# EEZ_CF-DIC_r3B8.net
KiCad netlist of a schematic drawn in EAGLE
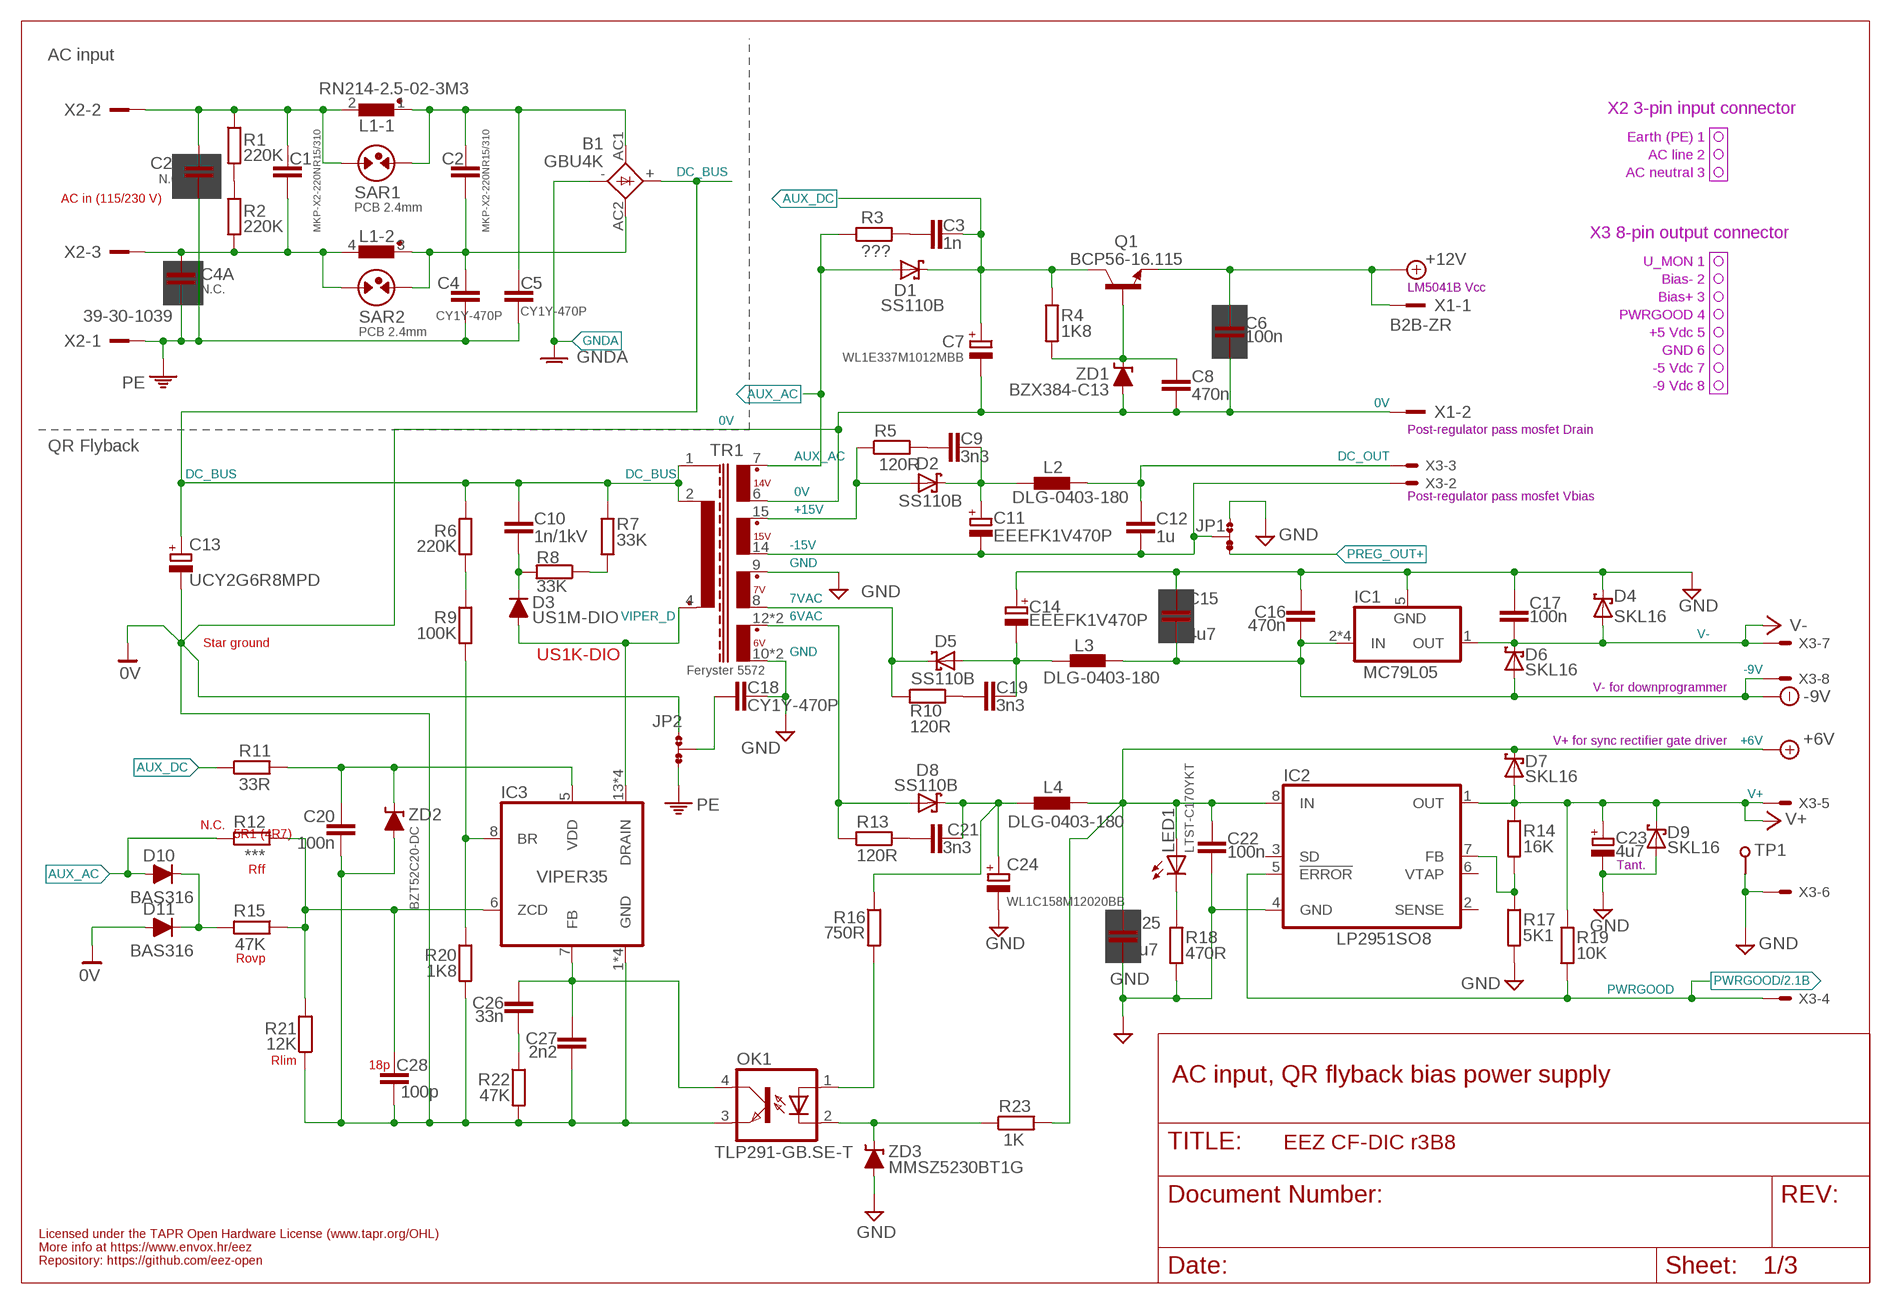
[diagram p0: schematic, sheet 1]
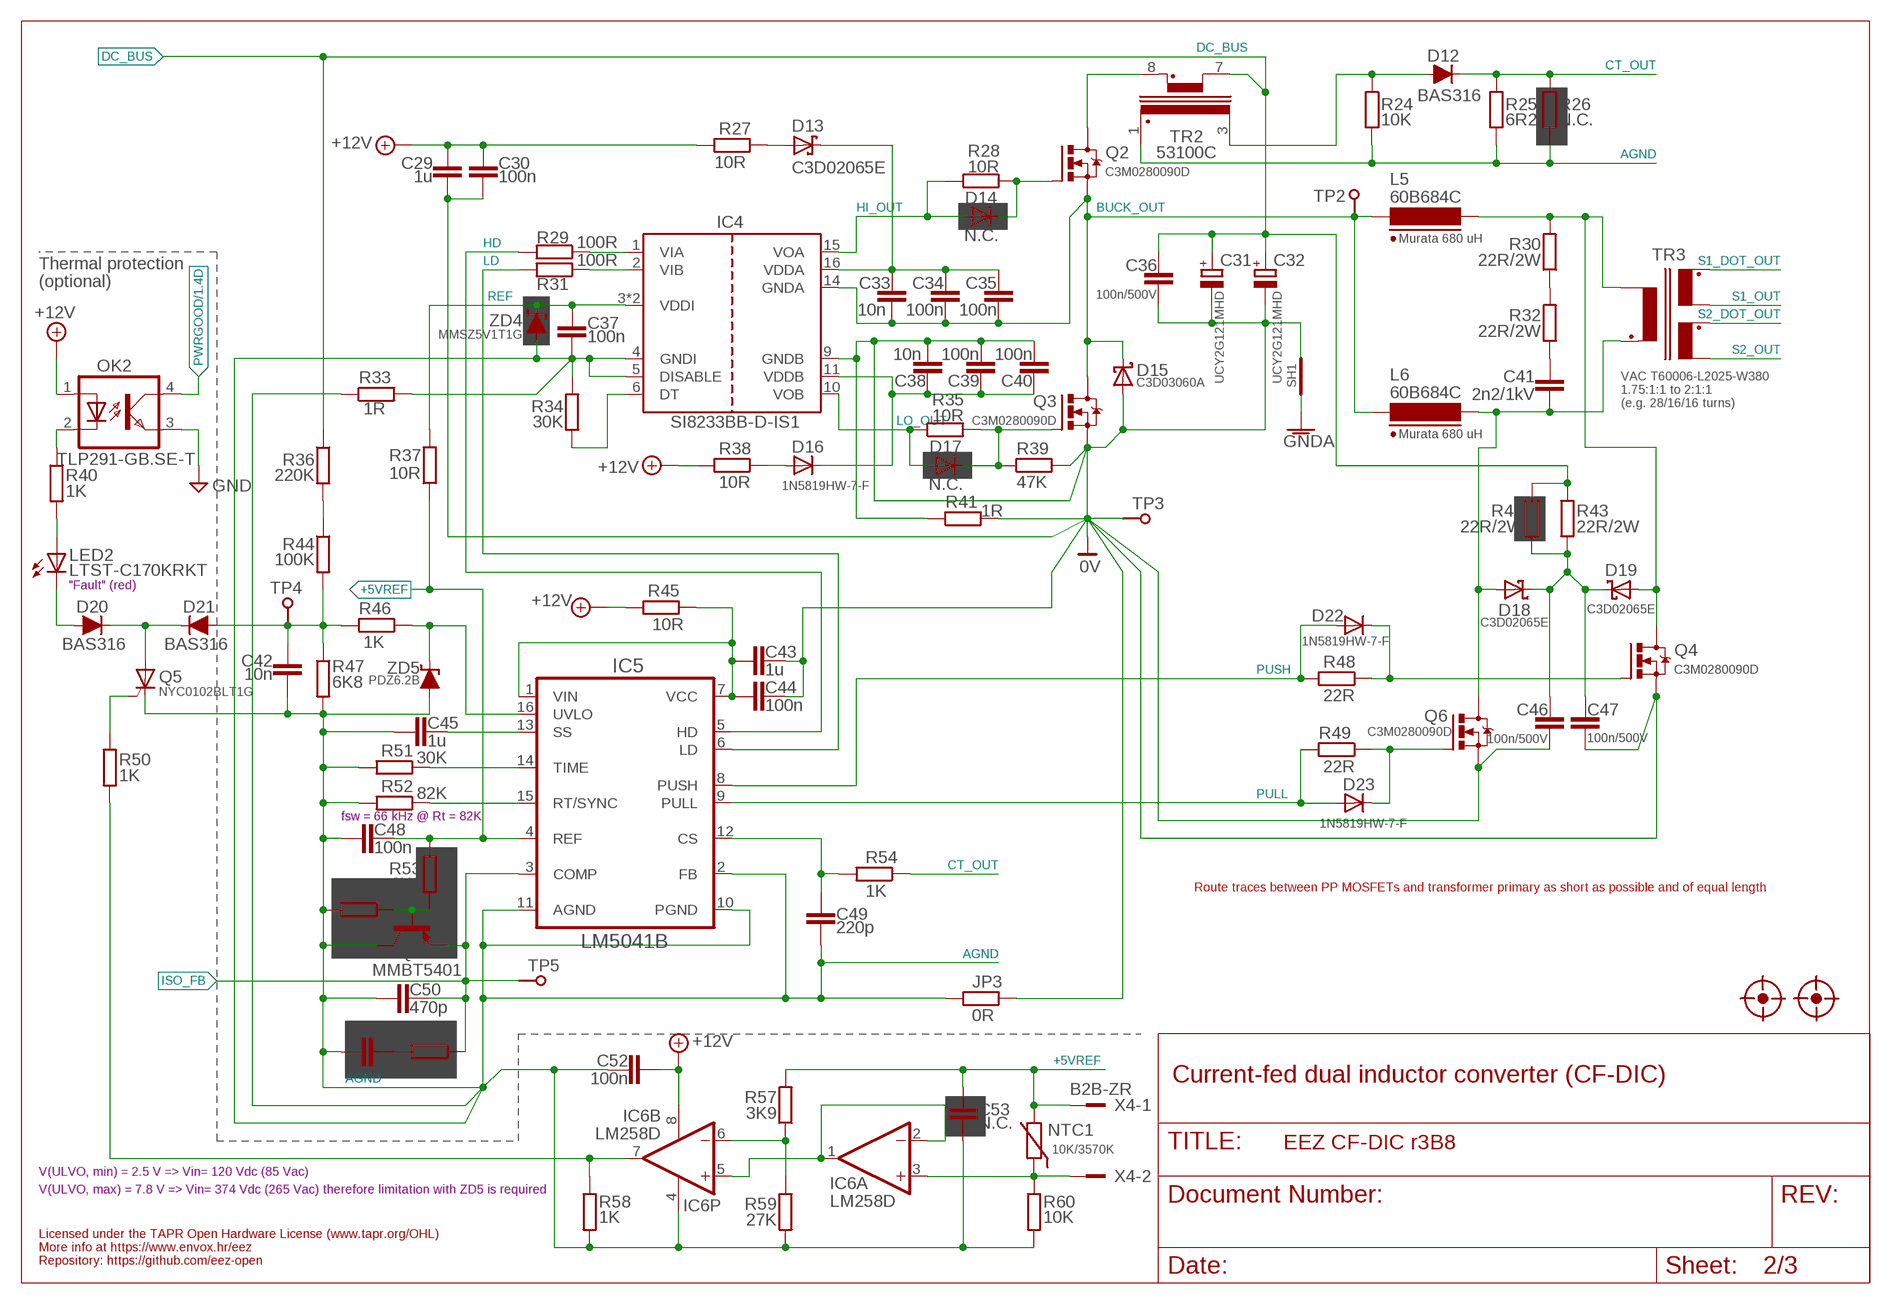
[diagram p1: schematic, sheet 2]
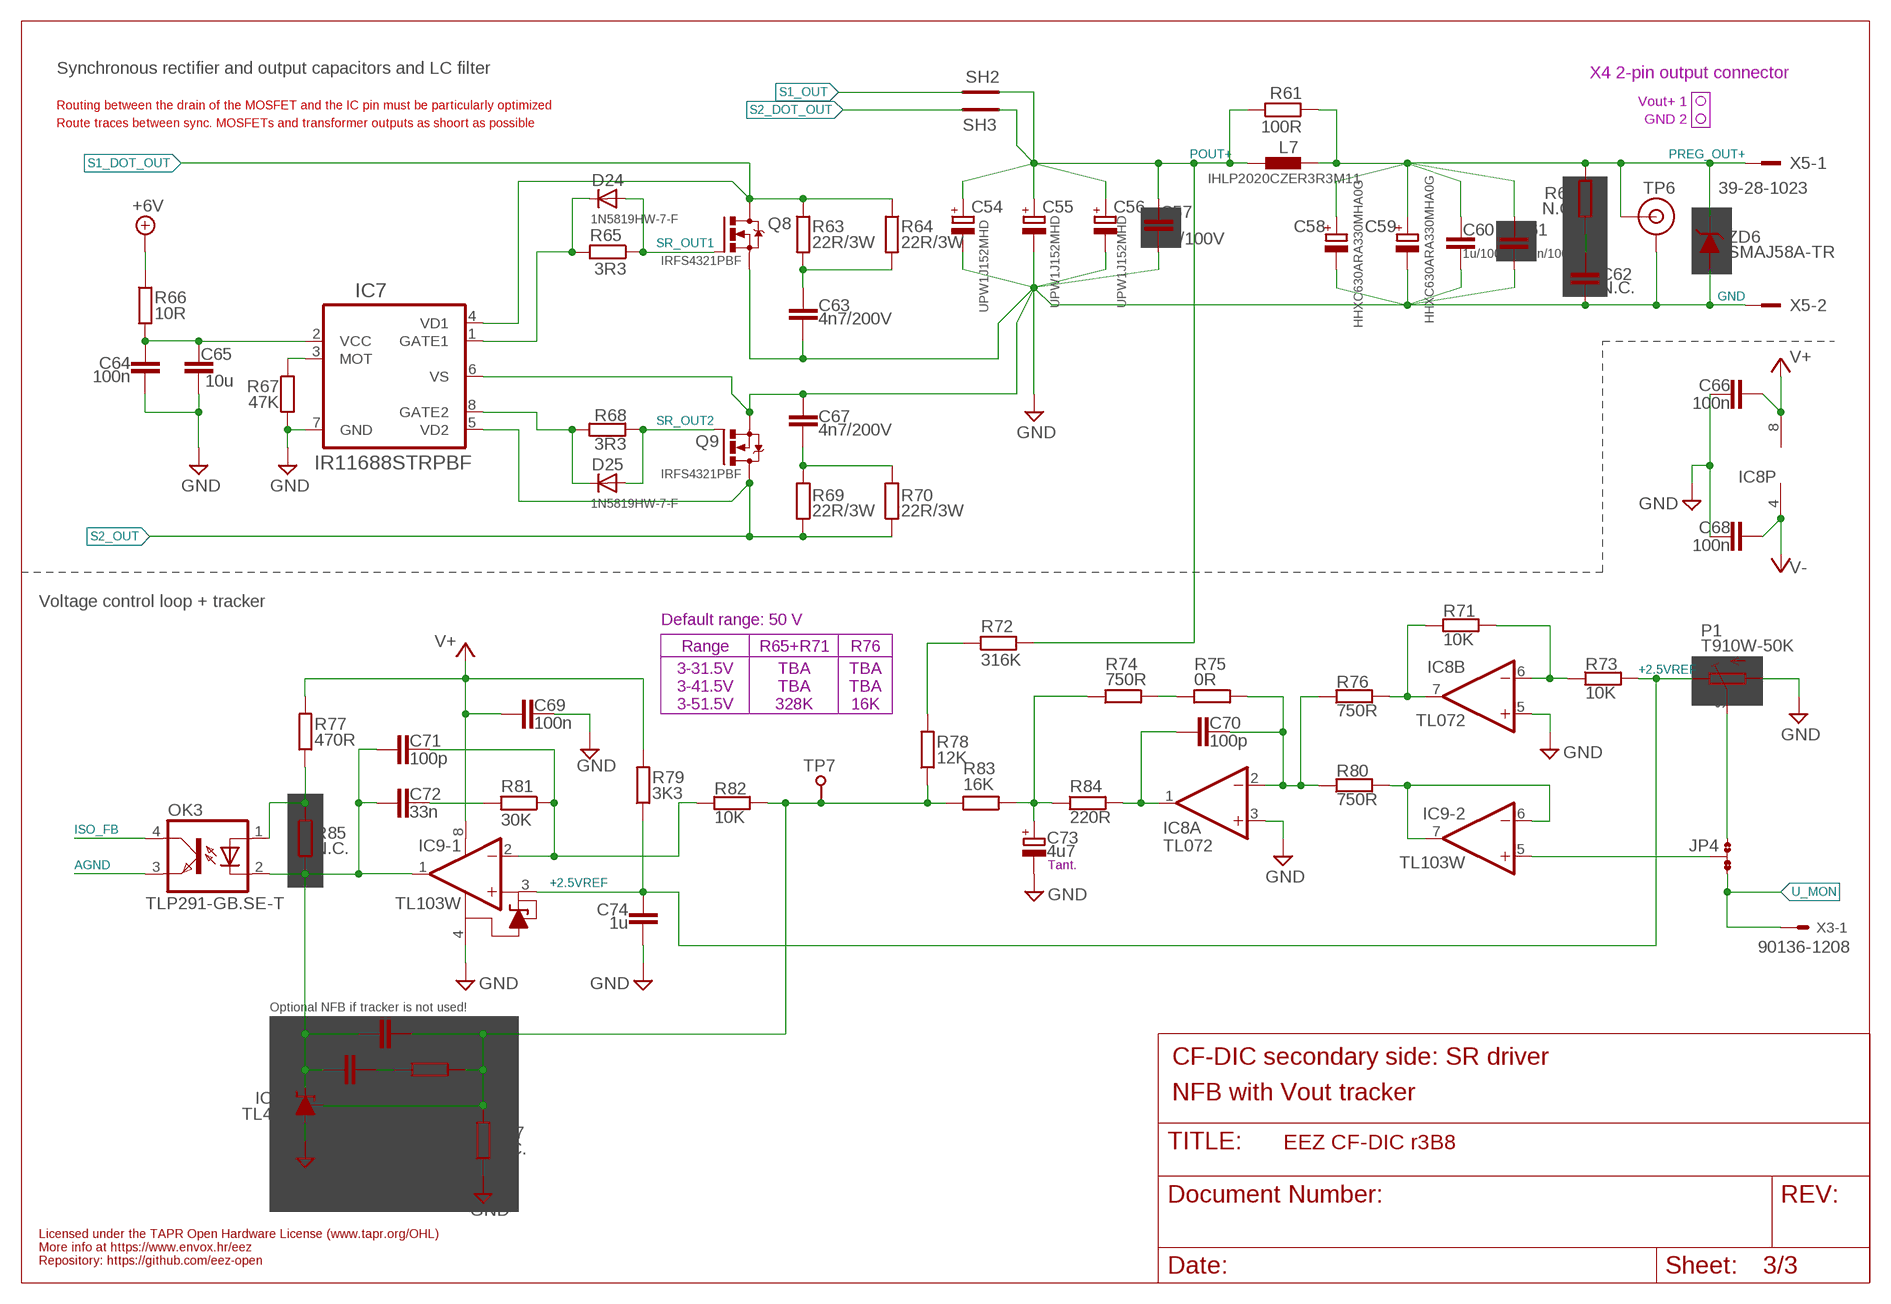
[diagram p2: schematic, sheet 3]

(export (version "E")
  (design (tool "Eeschema 10.0.6"))
  (components
    (comp (ref "C29")
      (value "1u")
      (footprint "eagle-import:C0805")
      (libsource (lib "eagle-import") (part "C-EUC0805"))
    )
    (comp (ref "C30")
      (value "100n")
      (footprint "eagle-import:C0603")
      (libsource (lib "eagle-import") (part "C-EUC0603"))
    )
    (comp (ref "C31")
      (value "UCY2G121MHD")
      (footprint "eagle-import:ECAP7.5_18")
      (libsource (lib "eagle-import") (part "ECAP7.5G_18MM"))
    )
    (comp (ref "C32")
      (value "UCY2G121MHD")
      (footprint "eagle-import:ECAP7.5_18")
      (libsource (lib "eagle-import") (part "ECAP7.5G_18MM"))
    )
    (comp (ref "C33")
      (value "10n")
      (footprint "eagle-import:C0603")
      (libsource (lib "eagle-import") (part "C-EUC0603"))
    )
    (comp (ref "C34")
      (value "100n")
      (footprint "eagle-import:C0603")
      (libsource (lib "eagle-import") (part "C-EUC0603"))
    )
    (comp (ref "C35")
      (value "100n")
      (footprint "eagle-import:C0603")
      (libsource (lib "eagle-import") (part "C-EUC0603"))
    )
    (comp (ref "C36")
      (value "100n/500V")
      (footprint "eagle-import:C1812")
      (libsource (lib "eagle-import") (part "C-EUC1812"))
    )
    (comp (ref "C37")
      (value "100n")
      (footprint "eagle-import:C0603")
      (libsource (lib "eagle-import") (part "C-EUC0603"))
    )
    (comp (ref "C38")
      (value "10n")
      (footprint "eagle-import:C0603")
      (libsource (lib "eagle-import") (part "C-EUC0603"))
    )
    (comp (ref "C39")
      (value "100n")
      (footprint "eagle-import:C0603")
      (libsource (lib "eagle-import") (part "C-EUC0603"))
    )
    (comp (ref "C40")
      (value "100n")
      (footprint "eagle-import:C0603")
      (libsource (lib "eagle-import") (part "C-EUC0603"))
    )
    (comp (ref "C41")
      (value "2n2/1kV")
      (footprint "eagle-import:C1210")
      (libsource (lib "eagle-import") (part "C-EUC1210"))
    )
    (comp (ref "C42")
      (value "10n")
      (footprint "eagle-import:C0603")
      (libsource (lib "eagle-import") (part "C-EUC0603"))
    )
    (comp (ref "C43")
      (value "1u")
      (footprint "eagle-import:C0805")
      (libsource (lib "eagle-import") (part "C-EUC0805"))
    )
    (comp (ref "C44")
      (value "100n")
      (footprint "eagle-import:C0603")
      (libsource (lib "eagle-import") (part "C-EUC0603"))
    )
    (comp (ref "C45")
      (value "1u")
      (footprint "eagle-import:C0805")
      (libsource (lib "eagle-import") (part "C-EUC0805"))
    )
    (comp (ref "C46")
      (value "100n/500V")
      (footprint "eagle-import:C1812")
      (libsource (lib "eagle-import") (part "C-EUC1812"))
    )
    (comp (ref "C47")
      (value "100n/500V")
      (footprint "eagle-import:C1812")
      (libsource (lib "eagle-import") (part "C-EUC1812"))
    )
    (comp (ref "C48")
      (value "100n")
      (footprint "eagle-import:C0603")
      (libsource (lib "eagle-import") (part "C-EUC0603"))
    )
    (comp (ref "C49")
      (value "220p")
      (footprint "eagle-import:C0805")
      (libsource (lib "eagle-import") (part "C-EUC0805"))
    )
    (comp (ref "C50")
      (value "470p")
      (footprint "eagle-import:C0805")
      (libsource (lib "eagle-import") (part "C-EUC0805"))
    )
    (comp (ref "C51")
      (value "N.C.")
      (footprint "eagle-import:C0805")
      (libsource (lib "eagle-import") (part "C-EUC0805"))
    )
    (comp (ref "C52")
      (value "100n")
      (footprint "eagle-import:C0603")
      (libsource (lib "eagle-import") (part "C-EUC0603"))
    )
    (comp (ref "C53")
      (value "N.C.")
      (footprint "eagle-import:C0603")
      (libsource (lib "eagle-import") (part "C-EUC0603"))
    )
    (comp (ref "D12")
      (value "BAS316")
      (footprint "eagle-import:SOD323-R")
      (libsource (lib "eagle-import") (part "DIODESOD323R"))
    )
    (comp (ref "D13")
      (value "C3D02065E")
      (footprint "eagle-import:TO252")
      (libsource (lib "eagle-import") (part "SCHOTTKY-SIC"))
    )
    (comp (ref "D14")
      (value "N.C.")
      (footprint "eagle-import:SOD323-W")
      (libsource (lib "eagle-import") (part "DIODE-SOD323-W"))
    )
    (comp (ref "D15")
      (value "C3D03060A")
      (footprint "eagle-import:TO220-2")
      (libsource (lib "eagle-import") (part "SCHOTTKY-TO220"))
    )
    (comp (ref "D16")
      (value "1N5819HW-7-F")
      (footprint "eagle-import:SOD323-W")
      (libsource (lib "eagle-import") (part "DIODE-SOD323-W"))
    )
    (comp (ref "D17")
      (value "N.C.")
      (footprint "eagle-import:SOD323-W")
      (libsource (lib "eagle-import") (part "DIODE-SOD323-W"))
    )
    (comp (ref "D18")
      (value "C3D02065E")
      (footprint "eagle-import:TO252")
      (libsource (lib "eagle-import") (part "SCHOTTKY-SIC"))
    )
    (comp (ref "D19")
      (value "C3D02065E")
      (footprint "eagle-import:TO252")
      (libsource (lib "eagle-import") (part "SCHOTTKY-SIC"))
    )
    (comp (ref "D20")
      (value "BAS316")
      (footprint "eagle-import:SOD323-R")
      (libsource (lib "eagle-import") (part "DIODESOD323R"))
    )
    (comp (ref "D21")
      (value "BAS316")
      (footprint "eagle-import:SOD323-R")
      (libsource (lib "eagle-import") (part "DIODESOD323R"))
    )
    (comp (ref "D22")
      (value "1N5819HW-7-F")
      (footprint "eagle-import:SOD323-W")
      (libsource (lib "eagle-import") (part "DIODE-SOD323-W"))
    )
    (comp (ref "D23")
      (value "1N5819HW-7-F")
      (footprint "eagle-import:SOD323-W")
      (libsource (lib "eagle-import") (part "DIODE-SOD323-W"))
    )
    (comp (ref "FM1")
      (value "FIDUCIAL_2")
      (footprint "eagle-import:FIDUCIAL_DUAL")
      (libsource (lib "eagle-import") (part "FIDUCIAL_2"))
    )
    (comp (ref "FM2")
      (value "FIDUCIAL_2")
      (footprint "eagle-import:FIDUCIAL_DUAL")
      (libsource (lib "eagle-import") (part "FIDUCIAL_2"))
    )
    (comp (ref "IC4")
      (value "SI8233BB-D-IS1")
      (footprint "eagle-import:SOIC-16")
      (libsource (lib "eagle-import") (part "SI8233"))
    )
    (comp (ref "IC5")
      (value "LM5041B")
      (footprint "eagle-import:MTC16")
      (fields (field (name "MANUFACTURER_PART_NUMBER") "lm5041mtcnopb"))
      (libsource (lib "eagle-import") (part "LM5041"))
    )
    (comp (ref "IC6")
      (value "LM258D")
      (footprint "eagle-import:SOIC127P600X173-8N")
      (libsource (lib "eagle-import") (part "TL072SOIC8"))
    )
    (comp (ref "JP3")
      (value "0R")
      (footprint "eagle-import:R0805")
      (libsource (lib "eagle-import") (part "R-EU_R0805"))
    )
    (comp (ref "L5")
      (value "60B684C")
      (footprint "eagle-import:MURATA_6000B")
      (libsource (lib "eagle-import") (part "EEZ_inductors_and_transformers_MURATA_6000B"))
    )
    (comp (ref "L6")
      (value "60B684C")
      (footprint "eagle-import:MURATA_6000B")
      (libsource (lib "eagle-import") (part "EEZ_inductors_and_transformers_MURATA_6000B"))
    )
    (comp (ref "LED2")
      (value "LTST-C170KRKT")
      (footprint "eagle-import:LED_0805")
      (libsource (lib "eagle-import") (part "LED0805"))
    )
    (comp (ref "NTC1")
      (value "10K/3570K")
      (footprint "eagle-import:R_0805")
      (libsource (lib "eagle-import") (part "NTCR_0805"))
    )
    (comp (ref "OK2")
      (value "TLP291-GB.SE-T")
      (footprint "eagle-import:SO4")
      (libsource (lib "eagle-import") (part "TLP291"))
    )
    (comp (ref "Q2")
      (value "C3M0280090D")
      (footprint "eagle-import:TO247BV")
      (libsource (lib "eagle-import") (part "IRFP240"))
    )
    (comp (ref "Q3")
      (value "C3M0280090D")
      (footprint "eagle-import:TO247BV")
      (libsource (lib "eagle-import") (part "IRFP240"))
    )
    (comp (ref "Q4")
      (value "C3M0280090D")
      (footprint "eagle-import:TO247BV")
      (libsource (lib "eagle-import") (part "IRFP240"))
    )
    (comp (ref "Q5")
      (value "NYC0102BLT1G")
      (footprint "eagle-import:SOT23")
      (libsource (lib "eagle-import") (part "NYC0102BLT1G"))
    )
    (comp (ref "Q6")
      (value "C3M0280090D")
      (footprint "eagle-import:TO247BV")
      (libsource (lib "eagle-import") (part "IRFP240"))
    )
    (comp (ref "Q7")
      (value "MMBT5401")
      (footprint "eagle-import:SOT23-BEC")
      (libsource (lib "eagle-import") (part "-PNP-SOT23-BECBC857B"))
    )
    (comp (ref "R24")
      (value "10K")
      (footprint "eagle-import:R0805")
      (libsource (lib "eagle-import") (part "R-EU_R0805"))
    )
    (comp (ref "R25")
      (value "6R2")
      (footprint "eagle-import:R0805")
      (libsource (lib "eagle-import") (part "R-EU_R0805"))
    )
    (comp (ref "R26")
      (value "N.C.")
      (footprint "eagle-import:R0805")
      (libsource (lib "eagle-import") (part "R-EU_R0805"))
    )
    (comp (ref "R27")
      (value "10R")
      (footprint "eagle-import:R0805")
      (libsource (lib "eagle-import") (part "R-EU_R0805"))
    )
    (comp (ref "R28")
      (value "10R")
      (footprint "eagle-import:R0805")
      (libsource (lib "eagle-import") (part "R-EU_R0805"))
    )
    (comp (ref "R29")
      (value "100R")
      (footprint "eagle-import:R0805")
      (libsource (lib "eagle-import") (part "R-EU_R0805"))
    )
    (comp (ref "R30")
      (value "22R/2W")
      (footprint "eagle-import:R2512")
      (libsource (lib "eagle-import") (part "R-EU_R2512"))
    )
    (comp (ref "R31")
      (value "100R")
      (footprint "eagle-import:R0805")
      (libsource (lib "eagle-import") (part "R-EU_R0805"))
    )
    (comp (ref "R32")
      (value "22R/2W")
      (footprint "eagle-import:R2512")
      (libsource (lib "eagle-import") (part "R-EU_R2512"))
    )
    (comp (ref "R33")
      (value "1R")
      (footprint "eagle-import:R0805")
      (libsource (lib "eagle-import") (part "R-EU_R0805"))
    )
    (comp (ref "R34")
      (value "30K")
      (footprint "eagle-import:R0805")
      (libsource (lib "eagle-import") (part "R-EU_R0805"))
    )
    (comp (ref "R35")
      (value "10R")
      (footprint "eagle-import:R0805")
      (libsource (lib "eagle-import") (part "R-EU_R0805"))
    )
    (comp (ref "R36")
      (value "220K")
      (footprint "eagle-import:R1206")
      (libsource (lib "eagle-import") (part "R-EU_R1206"))
    )
    (comp (ref "R37")
      (value "10R")
      (footprint "eagle-import:R0805")
      (libsource (lib "eagle-import") (part "R-EU_R0805"))
    )
    (comp (ref "R38")
      (value "10R")
      (footprint "eagle-import:R0805")
      (libsource (lib "eagle-import") (part "R-EU_R0805"))
    )
    (comp (ref "R39")
      (value "47K")
      (footprint "eagle-import:R0805")
      (libsource (lib "eagle-import") (part "R-EU_R0805"))
    )
    (comp (ref "R40")
      (value "1K")
      (footprint "eagle-import:R0805")
      (libsource (lib "eagle-import") (part "R-EU_R0805"))
    )
    (comp (ref "R41")
      (value "1R")
      (footprint "eagle-import:R0805")
      (libsource (lib "eagle-import") (part "R-EU_R0805"))
    )
    (comp (ref "R42")
      (value "22R/2W")
      (footprint "eagle-import:R2512")
      (libsource (lib "eagle-import") (part "R-EU_R2512"))
    )
    (comp (ref "R43")
      (value "22R/2W")
      (footprint "eagle-import:R2512")
      (libsource (lib "eagle-import") (part "R-EU_R2512"))
    )
    (comp (ref "R44")
      (value "100K")
      (footprint "eagle-import:R0805")
      (libsource (lib "eagle-import") (part "R-EU_R0805"))
    )
    (comp (ref "R45")
      (value "10R")
      (footprint "eagle-import:R0805")
      (libsource (lib "eagle-import") (part "R-EU_R0805"))
    )
    (comp (ref "R46")
      (value "1K")
      (footprint "eagle-import:R0805")
      (libsource (lib "eagle-import") (part "R-EU_R0805"))
    )
    (comp (ref "R47")
      (value "6K8")
      (footprint "eagle-import:R0805")
      (libsource (lib "eagle-import") (part "R-EU_R0805"))
    )
    (comp (ref "R48")
      (value "22R")
      (footprint "eagle-import:R0805")
      (libsource (lib "eagle-import") (part "R-EU_R0805"))
    )
    (comp (ref "R49")
      (value "22R")
      (footprint "eagle-import:R0805")
      (libsource (lib "eagle-import") (part "R-EU_R0805"))
    )
    (comp (ref "R50")
      (value "1K")
      (footprint "eagle-import:R0805")
      (libsource (lib "eagle-import") (part "R-EU_R0805"))
    )
    (comp (ref "R51")
      (value "30K")
      (footprint "eagle-import:R0805")
      (libsource (lib "eagle-import") (part "R-EU_R0805"))
    )
    (comp (ref "R52")
      (value "82K")
      (footprint "eagle-import:R0805")
      (libsource (lib "eagle-import") (part "R-EU_R0805"))
    )
    (comp (ref "R53")
      (value "6K8")
      (footprint "eagle-import:R0805")
      (libsource (lib "eagle-import") (part "R-EU_R0805"))
    )
    (comp (ref "R54")
      (value "1K")
      (footprint "eagle-import:R0805")
      (libsource (lib "eagle-import") (part "R-EU_R0805"))
    )
    (comp (ref "R55")
      (value "6K8")
      (footprint "eagle-import:R0805")
      (libsource (lib "eagle-import") (part "R-EU_R0805"))
    )
    (comp (ref "R56")
      (value "N.C.")
      (footprint "eagle-import:R0805")
      (libsource (lib "eagle-import") (part "R-EU_R0805"))
    )
    (comp (ref "R57")
      (value "3K9")
      (footprint "eagle-import:R0805")
      (libsource (lib "eagle-import") (part "R-EU_R0805"))
    )
    (comp (ref "R58")
      (value "1K")
      (footprint "eagle-import:R0805")
      (libsource (lib "eagle-import") (part "R-EU_R0805"))
    )
    (comp (ref "R59")
      (value "27K")
      (footprint "eagle-import:R0805")
      (libsource (lib "eagle-import") (part "R-EU_R0805"))
    )
    (comp (ref "R60")
      (value "10K")
      (footprint "eagle-import:R0805")
      (libsource (lib "eagle-import") (part "R-EU_R0805"))
    )
    (comp (ref "SH1")
      (value "SHORTNOHOLE")
      (footprint "eagle-import:SHORT_NOHOLE")
      (libsource (lib "eagle-import") (part "SHORTNOHOLE"))
    )
    (comp (ref "TP2")
      (value "PCB_TEST_TABSHIELD")
      (footprint "eagle-import:PCB_SHIELD_TAB")
      (libsource (lib "eagle-import") (part "PCB_TEST_TABSHIELD"))
    )
    (comp (ref "TP3")
      (value "PCB_TEST_TABSHIELD")
      (footprint "eagle-import:PCB_SHIELD_TAB")
      (libsource (lib "eagle-import") (part "PCB_TEST_TABSHIELD"))
    )
    (comp (ref "TP4")
      (value "PCB_TEST_TABSHIELD")
      (footprint "eagle-import:PCB_SHIELD_TAB")
      (libsource (lib "eagle-import") (part "PCB_TEST_TABSHIELD"))
    )
    (comp (ref "TP5")
      (value "PCB_TEST_TABSHIELD")
      (footprint "eagle-import:PCB_SHIELD_TAB")
      (libsource (lib "eagle-import") (part "PCB_TEST_TABSHIELD"))
    )
    (comp (ref "TR2")
      (value "53100C")
      (footprint "eagle-import:MURATA_5300")
      (libsource (lib "eagle-import") (part "MURATA_5300"))
    )
    (comp (ref "TR3")
      (value "VAC T60006-L2025-W380")
      (footprint "eagle-import:VAC_DUAL_SEC")
      (libsource (lib "eagle-import") (part "PCB_TRAFO_FLYBACK2-VAC"))
    )
    (comp (ref "X4")
      (value "B2B-ZR")
      (footprint "eagle-import:B2B-ZR")
      (libsource (lib "eagle-import") (part "B2B-ZR"))
    )
    (comp (ref "ZD4")
      (value "MMSZ5V1T1G")
      (footprint "eagle-import:SOD323-W")
      (libsource (lib "eagle-import") (part "ZENER-DIODESOD323"))
    )
    (comp (ref "ZD5")
      (value "PDZ6.2B")
      (footprint "eagle-import:SOD323-W")
      (libsource (lib "eagle-import") (part "ZENER-DIODESOD323"))
    )
    (comp (ref "C54")
      (value "UPW1J152MHD")
      (footprint "eagle-import:ECAP7.5_18")
      (libsource (lib "eagle-import") (part "ECAP7.5G_18MM"))
    )
    (comp (ref "C55")
      (value "UPW1J152MHD")
      (footprint "eagle-import:ECAP7.5_18")
      (libsource (lib "eagle-import") (part "ECAP7.5G_18MM"))
    )
    (comp (ref "C56")
      (value "UPW1J152MHD")
      (footprint "eagle-import:ECAP7.5_18")
      (libsource (lib "eagle-import") (part "ECAP7.5G_18MM"))
    )
    (comp (ref "C57")
      (value "1u/100V")
      (footprint "eagle-import:C1206")
      (libsource (lib "eagle-import") (part "C-EUC1206"))
    )
    (comp (ref "C58")
      (value "HHXC630ARA330MHA0G ")
      (footprint "eagle-import:CAPAE830X1050N")
      (fields
        (field (name "MPN") "EEE-FK1J470P")
        (field (name "TOLERANCE") "±20 %")
        (field (name "MPN_1") "EEE-FK1J470P")
        (field (name "OC_FARNELL") "9696032  ")
        (field (name "OC_NEWARK") "96K9403")
        (field (name "PACKAGE") "CASE-F")
        (field (name "SUPPLIER") "PANASONIC")
        (field (name "TOLERANCE_1") "±20 %")
        (field (name "VOLTAGERATING") "63 V")
      )
      (libsource (lib "eagle-import") (part "EEE--CASE-FFK1J470P"))
    )
    (comp (ref "C59")
      (value "HHXC630ARA330MHA0G")
      (footprint "eagle-import:CAPAE830X1050N")
      (fields (field (name "MPN") "EEE-FK1J470P") (field (name "TOLERANCE") "±20 %"))
      (libsource (lib "eagle-import") (part "EEE--CASE-FFK1J470P"))
    )
    (comp (ref "C60")
      (value "1u/100V")
      (footprint "eagle-import:C1206")
      (libsource (lib "eagle-import") (part "C-EUC1206"))
    )
    (comp (ref "C61")
      (value "100n/100V")
      (footprint "eagle-import:C0805")
      (libsource (lib "eagle-import") (part "C-EUC0805"))
    )
    (comp (ref "C62")
      (value "N.C.")
      (footprint "eagle-import:C1206")
      (libsource (lib "eagle-import") (part "C-EUC1206"))
    )
    (comp (ref "C63")
      (value "4n7/200V")
      (footprint "eagle-import:C1206")
      (libsource (lib "eagle-import") (part "C-EUC1206"))
    )
    (comp (ref "C64")
      (value "100n")
      (footprint "eagle-import:C0603")
      (libsource (lib "eagle-import") (part "C-EUC0603"))
    )
    (comp (ref "C65")
      (value "10u")
      (footprint "eagle-import:C1210")
      (libsource (lib "eagle-import") (part "C-EUC1210"))
    )
    (comp (ref "C66")
      (value "100n")
      (footprint "eagle-import:C0603")
      (libsource (lib "eagle-import") (part "C-EUC0603"))
    )
    (comp (ref "C67")
      (value "4n7/200V")
      (footprint "eagle-import:C1206")
      (libsource (lib "eagle-import") (part "C-EUC1206"))
    )
    (comp (ref "C68")
      (value "100n")
      (footprint "eagle-import:C0603")
      (libsource (lib "eagle-import") (part "C-EUC0603"))
    )
    (comp (ref "C69")
      (value "100n")
      (footprint "eagle-import:C0603")
      (libsource (lib "eagle-import") (part "C-EUC0603"))
    )
    (comp (ref "C70")
      (value "100p")
      (footprint "eagle-import:C0805")
      (libsource (lib "eagle-import") (part "C-EUC0805"))
    )
    (comp (ref "C71")
      (value "100p")
      (footprint "eagle-import:C0805")
      (libsource (lib "eagle-import") (part "C-EUC0805"))
    )
    (comp (ref "C72")
      (value "33n")
      (footprint "eagle-import:C0805")
      (libsource (lib "eagle-import") (part "C-EUC0805"))
    )
    (comp (ref "C73")
      (value "4u7")
      (footprint "eagle-import:EC1206")
      (libsource (lib "eagle-import") (part "ECAP1206"))
    )
    (comp (ref "C74")
      (value "1u")
      (footprint "eagle-import:C0805")
      (libsource (lib "eagle-import") (part "C-EUC0805"))
    )
    (comp (ref "C75")
      (value "N.C.")
      (footprint "eagle-import:C0805")
      (libsource (lib "eagle-import") (part "C-EUC0805"))
    )
    (comp (ref "C76")
      (value "N.C.")
      (footprint "eagle-import:C0805")
      (libsource (lib "eagle-import") (part "C-EUC0805"))
    )
    (comp (ref "D24")
      (value "1N5819HW-7-F")
      (footprint "eagle-import:SOD323-W")
      (libsource (lib "eagle-import") (part "DIODE-SOD323-W"))
    )
    (comp (ref "D25")
      (value "1N5819HW-7-F")
      (footprint "eagle-import:SOD323-W")
      (libsource (lib "eagle-import") (part "DIODE-SOD323-W"))
    )
    (comp (ref "IC7")
      (value "IR11688STRPBF")
      (footprint "eagle-import:SO8")
      (libsource (lib "eagle-import") (part "IR11688"))
    )
    (comp (ref "IC8")
      (value "TL072")
      (footprint "eagle-import:SOIC127P600X173-8N")
      (libsource (lib "eagle-import") (part "TL072SOIC8"))
    )
    (comp (ref "IC9")
      (value "TL103W")
      (footprint "eagle-import:SOIC127P600X173-8N")
      (libsource (lib "eagle-import") (part "TL103W"))
    )
    (comp (ref "IC10")
      (value "TL431")
      (footprint "eagle-import:SOT103P240X110-3N")
      (libsource (lib "eagle-import") (part "TL431"))
    )
    (comp (ref "JP4")
      (value "JP3-CUT")
      (footprint "eagle-import:JP3-CUT")
      (libsource (lib "eagle-import") (part "JP3-CUT"))
    )
    (comp (ref "L7")
      (value "IHLP2020CZER3R3M11")
      (footprint "eagle-import:IHLP-2020BZ-11")
      (libsource (lib "eagle-import") (part "EEZ_inductors_and_transformers_IHLP-2020BZ-11"))
    )
    (comp (ref "OK3")
      (value "TLP291-GB.SE-T")
      (footprint "eagle-import:SO4")
      (libsource (lib "eagle-import") (part "TLP291"))
    )
    (comp (ref "P1")
      (value "T910W-50K")
      (footprint "eagle-import:S64W")
      (libsource (lib "eagle-import") (part "TPOT-S64W"))
    )
    (comp (ref "Q8")
      (value "IRFS4321PBF")
      (footprint "eagle-import:TO263")
      (libsource (lib "eagle-import") (part "N-MOSFETTO263"))
    )
    (comp (ref "Q9")
      (value "IRFS4321PBF")
      (footprint "eagle-import:TO263")
      (libsource (lib "eagle-import") (part "N-MOSFETTO263"))
    )
    (comp (ref "R61")
      (value "100R")
      (footprint "eagle-import:R0805")
      (libsource (lib "eagle-import") (part "R-EU_R0805"))
    )
    (comp (ref "R62")
      (value "N.C.")
      (footprint "eagle-import:R1210")
      (libsource (lib "eagle-import") (part "R-EU_R1210"))
    )
    (comp (ref "R63")
      (value "22R/3W")
      (footprint "eagle-import:R2512")
      (libsource (lib "eagle-import") (part "R-EU_R2512"))
    )
    (comp (ref "R64")
      (value "22R/3W")
      (footprint "eagle-import:R2512")
      (libsource (lib "eagle-import") (part "R-EU_R2512"))
    )
    (comp (ref "R65")
      (value "3R3")
      (footprint "eagle-import:R0805")
      (libsource (lib "eagle-import") (part "R-EU_R0805"))
    )
    (comp (ref "R66")
      (value "10R")
      (footprint "eagle-import:R0805")
      (libsource (lib "eagle-import") (part "R-EU_R0805"))
    )
    (comp (ref "R67")
      (value "47K")
      (footprint "eagle-import:R0805")
      (libsource (lib "eagle-import") (part "R-EU_R0805"))
    )
    (comp (ref "R68")
      (value "3R3")
      (footprint "eagle-import:R0805")
      (libsource (lib "eagle-import") (part "R-EU_R0805"))
    )
    (comp (ref "R69")
      (value "22R/3W")
      (footprint "eagle-import:R2512")
      (libsource (lib "eagle-import") (part "R-EU_R2512"))
    )
    (comp (ref "R70")
      (value "22R/3W")
      (footprint "eagle-import:R2512")
      (libsource (lib "eagle-import") (part "R-EU_R2512"))
    )
    (comp (ref "R71")
      (value "10K")
      (footprint "eagle-import:R0805")
      (libsource (lib "eagle-import") (part "R-EU_R0805"))
    )
    (comp (ref "R72")
      (value "316K")
      (footprint "eagle-import:R0805")
      (libsource (lib "eagle-import") (part "R-EU_R0805"))
    )
    (comp (ref "R73")
      (value "10K")
      (footprint "eagle-import:R0805")
      (libsource (lib "eagle-import") (part "R-EU_R0805"))
    )
    (comp (ref "R74")
      (value "750R")
      (footprint "eagle-import:R0805")
      (libsource (lib "eagle-import") (part "R-EU_R0805"))
    )
    (comp (ref "R75")
      (value "0R")
      (footprint "eagle-import:R0805")
      (libsource (lib "eagle-import") (part "R-EU_R0805"))
    )
    (comp (ref "R76")
      (value "750R")
      (footprint "eagle-import:R0805")
      (libsource (lib "eagle-import") (part "R-EU_R0805"))
    )
    (comp (ref "R77")
      (value "470R")
      (footprint "eagle-import:R0805")
      (libsource (lib "eagle-import") (part "R-EU_R0805"))
    )
    (comp (ref "R78")
      (value "12K")
      (footprint "eagle-import:R0805")
      (libsource (lib "eagle-import") (part "R-EU_R0805"))
    )
    (comp (ref "R79")
      (value "3K3")
      (footprint "eagle-import:R0805")
      (libsource (lib "eagle-import") (part "R-EU_R0805"))
    )
    (comp (ref "R80")
      (value "750R")
      (footprint "eagle-import:R0805")
      (libsource (lib "eagle-import") (part "R-EU_R0805"))
    )
    (comp (ref "R81")
      (value "30K")
      (footprint "eagle-import:R0805")
      (libsource (lib "eagle-import") (part "R-EU_R0805"))
    )
    (comp (ref "R82")
      (value "10K")
      (footprint "eagle-import:R0805")
      (libsource (lib "eagle-import") (part "R-EU_R0805"))
    )
    (comp (ref "R83")
      (value "16K")
      (footprint "eagle-import:R0805")
      (libsource (lib "eagle-import") (part "R-EU_R0805"))
    )
    (comp (ref "R84")
      (value "220R")
      (footprint "eagle-import:R0805")
      (libsource (lib "eagle-import") (part "R-EU_R0805"))
    )
    (comp (ref "R85")
      (value "N.C.")
      (footprint "eagle-import:R0805")
      (libsource (lib "eagle-import") (part "R-EU_R0805"))
    )
    (comp (ref "R86")
      (value "N.C.")
      (footprint "eagle-import:R0805")
      (libsource (lib "eagle-import") (part "R-EU_R0805"))
    )
    (comp (ref "R87")
      (value "N.C.")
      (footprint "eagle-import:R0805")
      (libsource (lib "eagle-import") (part "R-EU_R0805"))
    )
    (comp (ref "SH2")
      (value "SHORTNOHOLE")
      (footprint "eagle-import:SHORT_NOHOLE")
      (libsource (lib "eagle-import") (part "SHORTNOHOLE"))
    )
    (comp (ref "SH3")
      (value "SHORTNOHOLE")
      (footprint "eagle-import:SHORT_NOHOLE")
      (libsource (lib "eagle-import") (part "SHORTNOHOLE"))
    )
    (comp (ref "TP6")
      (value "TEST_POINT-2")
      (footprint "eagle-import:TP_1.1MM_2")
      (libsource (lib "eagle-import") (part "TEST_POINT-2"))
    )
    (comp (ref "TP7")
      (value "PCB_TEST_TABSHIELD")
      (footprint "eagle-import:PCB_SHIELD_TAB")
      (libsource (lib "eagle-import") (part "PCB_TEST_TABSHIELD"))
    )
    (comp (ref "X3")
      (value "90136-1208")
      (footprint "eagle-import:70543-08")
      (libsource (lib "eagle-import") (part "C-GRID-08-70543"))
    )
    (comp (ref "X5")
      (value "39-28-1023")
      (footprint "eagle-import:MINIFIT_5566-02A")
      (libsource (lib "eagle-import") (part "MINIFIT_5566-02A"))
    )
    (comp (ref "ZD6")
      (value "SMAJ58A-TR")
      (footprint "eagle-import:DO214AC")
      (libsource (lib "eagle-import") (part "PSMAXX"))
    )
    (comp (ref "B1")
      (value "GBU4K")
      (footprint "eagle-import:GBU4K_CRE")
      (libsource (lib "eagle-import") (part "BRIDGE-CREEPAGE"))
    )
    (comp (ref "C1")
      (value "MKP-X2-220NR15/310")
      (footprint "eagle-import:C150-072X183")
      (libsource (lib "eagle-import") (part "C-EU150-072X183"))
    )
    (comp (ref "C2")
      (value "MKP-X2-220NR15/310")
      (footprint "eagle-import:C150-072X183")
      (libsource (lib "eagle-import") (part "C-EU150-072X183"))
    )
    (comp (ref "C2A")
      (value "N.C.")
      (footprint "eagle-import:CY075-032X103")
      (libsource (lib "eagle-import") (part "C-EUCY"))
    )
    (comp (ref "C3")
      (value "1n")
      (footprint "eagle-import:C0805")
      (libsource (lib "eagle-import") (part "C-EUC0805"))
    )
    (comp (ref "C4")
      (value "CY1Y-470P")
      (footprint "eagle-import:CY075-032X103")
      (libsource (lib "eagle-import") (part "C-EUCY"))
    )
    (comp (ref "C4A")
      (value "N.C.")
      (footprint "eagle-import:CY075-032X103")
      (libsource (lib "eagle-import") (part "C-EUCY"))
    )
    (comp (ref "C5")
      (value "CY1Y-470P")
      (footprint "eagle-import:CY075-032X103")
      (libsource (lib "eagle-import") (part "C-EUCY"))
    )
    (comp (ref "C6")
      (value "100n")
      (footprint "eagle-import:C0603")
      (libsource (lib "eagle-import") (part "C-EUC0603"))
    )
    (comp (ref "C7")
      (value "WL1E337M1012MBB")
      (footprint "eagle-import:CAPAE660X610N")
      (libsource (lib "eagle-import") (part "ECAPPANASONIC_H"))
    )
    (comp (ref "C8")
      (value "470n")
      (footprint "eagle-import:C0805")
      (libsource (lib "eagle-import") (part "C-EUC0805"))
    )
    (comp (ref "C9")
      (value "3n3")
      (footprint "eagle-import:C0805")
      (libsource (lib "eagle-import") (part "C-EUC0805"))
    )
    (comp (ref "C10")
      (value "1n/1kV")
      (footprint "eagle-import:C1210")
      (libsource (lib "eagle-import") (part "C-EUC1210"))
    )
    (comp (ref "C11")
      (value "EEEFK1V470P")
      (footprint "eagle-import:CAPAE660X610N")
      (libsource (lib "eagle-import") (part "ECAPPANASONIC_H"))
    )
    (comp (ref "C12")
      (value "1u")
      (footprint "eagle-import:C0805")
      (libsource (lib "eagle-import") (part "C-EUC0805"))
    )
    (comp (ref "C13")
      (value "UCY2G6R8MPD")
      (footprint "eagle-import:ECAP5_10.5")
      (libsource (lib "eagle-import") (part "ECAP5G_10.5MM"))
    )
    (comp (ref "C14")
      (value "EEEFK1V470P")
      (footprint "eagle-import:CAPAE660X610N")
      (libsource (lib "eagle-import") (part "ECAPPANASONIC_H"))
    )
    (comp (ref "C15")
      (value "4u7")
      (footprint "eagle-import:C1206")
      (libsource (lib "eagle-import") (part "C-EUC1206"))
    )
    (comp (ref "C16")
      (value "470n")
      (footprint "eagle-import:C0805")
      (libsource (lib "eagle-import") (part "C-EUC0805"))
    )
    (comp (ref "C17")
      (value "100n")
      (footprint "eagle-import:C0603")
      (libsource (lib "eagle-import") (part "C-EUC0603"))
    )
    (comp (ref "C18")
      (value "CY1Y-470P")
      (footprint "eagle-import:CY075-032X103")
      (libsource (lib "eagle-import") (part "C-EUCY"))
    )
    (comp (ref "C19")
      (value "3n3")
      (footprint "eagle-import:C0805")
      (libsource (lib "eagle-import") (part "C-EUC0805"))
    )
    (comp (ref "C20")
      (value "100n")
      (footprint "eagle-import:C0603")
      (libsource (lib "eagle-import") (part "C-EUC0603"))
    )
    (comp (ref "C21")
      (value "3n3")
      (footprint "eagle-import:C0805")
      (libsource (lib "eagle-import") (part "C-EUC0805"))
    )
    (comp (ref "C22")
      (value "100n")
      (footprint "eagle-import:C0603")
      (libsource (lib "eagle-import") (part "C-EUC0603"))
    )
    (comp (ref "C23")
      (value "4u7")
      (footprint "eagle-import:EC1206")
      (libsource (lib "eagle-import") (part "ECAP1206"))
    )
    (comp (ref "C24")
      (value "WL1C158M12020BB")
      (footprint "eagle-import:ECAP5_10.5")
      (libsource (lib "eagle-import") (part "ECAP5G_10.5MM"))
    )
    (comp (ref "C25")
      (value "4u7")
      (footprint "eagle-import:C1206")
      (libsource (lib "eagle-import") (part "C-EUC1206"))
    )
    (comp (ref "C26")
      (value "33n")
      (footprint "eagle-import:C0805")
      (libsource (lib "eagle-import") (part "C-EUC0805"))
    )
    (comp (ref "C27")
      (value "2n2")
      (footprint "eagle-import:C0805")
      (libsource (lib "eagle-import") (part "C-EUC0805"))
    )
    (comp (ref "C28")
      (value "100p")
      (footprint "eagle-import:C0805")
      (libsource (lib "eagle-import") (part "C-EUC0805"))
    )
    (comp (ref "D1")
      (value "SS110B")
      (footprint "eagle-import:SMB")
      (libsource (lib "eagle-import") (part "SCHOTTKYSMB"))
    )
    (comp (ref "D2")
      (value "SS110B")
      (footprint "eagle-import:SMB")
      (libsource (lib "eagle-import") (part "SCHOTTKYSMB"))
    )
    (comp (ref "D3")
      (value "US1M-DIO")
      (footprint "eagle-import:DO214AA")
      (libsource (lib "eagle-import") (part "DIODEDO214AA"))
    )
    (comp (ref "D4")
      (value "SKL16")
      (footprint "eagle-import:SOD123")
      (libsource (lib "eagle-import") (part "SCHOTTKYSOD123"))
    )
    (comp (ref "D5")
      (value "SS110B")
      (footprint "eagle-import:SMB")
      (libsource (lib "eagle-import") (part "SCHOTTKYSMB"))
    )
    (comp (ref "D6")
      (value "SKL16")
      (footprint "eagle-import:SOD123")
      (libsource (lib "eagle-import") (part "SCHOTTKYSOD123"))
    )
    (comp (ref "D7")
      (value "SKL16")
      (footprint "eagle-import:SOD123")
      (libsource (lib "eagle-import") (part "SCHOTTKYSOD123"))
    )
    (comp (ref "D8")
      (value "SS110B")
      (footprint "eagle-import:SMB")
      (libsource (lib "eagle-import") (part "SCHOTTKYSMB"))
    )
    (comp (ref "D9")
      (value "SKL16")
      (footprint "eagle-import:SOD123")
      (libsource (lib "eagle-import") (part "SCHOTTKYSOD123"))
    )
    (comp (ref "D10")
      (value "BAS316")
      (footprint "eagle-import:SOD323-R")
      (libsource (lib "eagle-import") (part "DIODESOD323R"))
    )
    (comp (ref "D11")
      (value "BAS316")
      (footprint "eagle-import:SOD323-R")
      (libsource (lib "eagle-import") (part "DIODESOD323R"))
    )
    (comp (ref "IC1")
      (value "MC79L05")
      (footprint "eagle-import:SOIC127P600X173-8N")
      (libsource (lib "eagle-import") (part "MC79LXXSOIC"))
    )
    (comp (ref "IC2")
      (value "LP2951SO8")
      (footprint "eagle-import:SOIC127P600X175-8N")
      (libsource (lib "eagle-import") (part "LP2951SO8"))
    )
    (comp (ref "IC3")
      (value "VIPER35")
      (footprint "eagle-import:SOIC-16")
      (libsource (lib "eagle-import") (part "VIPER35"))
    )
    (comp (ref "JP1")
      (value "JP3-CUT")
      (footprint "eagle-import:JP3-CUT")
      (libsource (lib "eagle-import") (part "JP3-CUT"))
    )
    (comp (ref "JP2")
      (value "JP3-CUT")
      (footprint "eagle-import:JP3-CUT")
      (libsource (lib "eagle-import") (part "JP3-CUT"))
    )
    (comp (ref "L1")
      (value "RN214-2.5-02-3M3")
      (footprint "eagle-import:RN214")
      (fields (field (name "FARNELL") "1191518"))
      (libsource (lib "eagle-import") (part "EEZ_inductors_and_transformers_RN214"))
    )
    (comp (ref "L2")
      (value "DLG-0403-180")
      (footprint "eagle-import:DE0403")
      (libsource (lib "eagle-import") (part "DE0403"))
    )
    (comp (ref "L3")
      (value "DLG-0403-180")
      (footprint "eagle-import:DE0403")
      (libsource (lib "eagle-import") (part "DE0403"))
    )
    (comp (ref "L4")
      (value "DLG-0403-180")
      (footprint "eagle-import:DE0403")
      (libsource (lib "eagle-import") (part "DE0403"))
    )
    (comp (ref "LED1")
      (value "LTST-C170YKT")
      (footprint "eagle-import:LED_0805")
      (libsource (lib "eagle-import") (part "LED0805"))
    )
    (comp (ref "OK1")
      (value "TLP291-GB.SE-T")
      (footprint "eagle-import:SO4")
      (libsource (lib "eagle-import") (part "TLP291"))
    )
    (comp (ref "Q1")
      (value "BCP56-16.115")
      (footprint "eagle-import:SOT230P700X180-4N")
      (libsource (lib "eagle-import") (part "BCP56"))
    )
    (comp (ref "R1")
      (value "220K")
      (footprint "eagle-import:R1206")
      (libsource (lib "eagle-import") (part "R-EU_R1206"))
    )
    (comp (ref "R2")
      (value "220K")
      (footprint "eagle-import:R1206")
      (libsource (lib "eagle-import") (part "R-EU_R1206"))
    )
    (comp (ref "R3")
      (value "???")
      (footprint "eagle-import:R0805")
      (libsource (lib "eagle-import") (part "R-EU_R0805"))
    )
    (comp (ref "R4")
      (value "1K8")
      (footprint "eagle-import:R0805")
      (libsource (lib "eagle-import") (part "R-EU_R0805"))
    )
    (comp (ref "R5")
      (value "120R")
      (footprint "eagle-import:R0805")
      (libsource (lib "eagle-import") (part "R-EU_R0805"))
    )
    (comp (ref "R6")
      (value "220K")
      (footprint "eagle-import:R1206")
      (libsource (lib "eagle-import") (part "R-EU_R1206"))
    )
    (comp (ref "R7")
      (value "33K")
      (footprint "eagle-import:R1210")
      (libsource (lib "eagle-import") (part "R-EU_R1210"))
    )
    (comp (ref "R8")
      (value "33K")
      (footprint "eagle-import:R1210")
      (libsource (lib "eagle-import") (part "R-EU_R1210"))
    )
    (comp (ref "R9")
      (value "100K")
      (footprint "eagle-import:R0805")
      (libsource (lib "eagle-import") (part "R-EU_R0805"))
    )
    (comp (ref "R10")
      (value "120R")
      (footprint "eagle-import:R0805")
      (libsource (lib "eagle-import") (part "R-EU_R0805"))
    )
    (comp (ref "R11")
      (value "33R")
      (footprint "eagle-import:R0805")
      (libsource (lib "eagle-import") (part "R-EU_R0805"))
    )
    (comp (ref "R12")
      (value "***")
      (footprint "eagle-import:R0805")
      (libsource (lib "eagle-import") (part "R-EU_R0805"))
    )
    (comp (ref "R13")
      (value "120R")
      (footprint "eagle-import:R0805")
      (libsource (lib "eagle-import") (part "R-EU_R0805"))
    )
    (comp (ref "R14")
      (value "16K")
      (footprint "eagle-import:R0805")
      (libsource (lib "eagle-import") (part "R-EU_R0805"))
    )
    (comp (ref "R15")
      (value "47K")
      (footprint "eagle-import:R0805")
      (libsource (lib "eagle-import") (part "R-EU_R0805"))
    )
    (comp (ref "R16")
      (value "750R")
      (footprint "eagle-import:R0805")
      (libsource (lib "eagle-import") (part "R-EU_R0805"))
    )
    (comp (ref "R17")
      (value "5K1")
      (footprint "eagle-import:R0805")
      (libsource (lib "eagle-import") (part "R-EU_R0805"))
    )
    (comp (ref "R18")
      (value "470R")
      (footprint "eagle-import:R0805")
      (libsource (lib "eagle-import") (part "R-EU_R0805"))
    )
    (comp (ref "R19")
      (value "10K")
      (footprint "eagle-import:R0805")
      (libsource (lib "eagle-import") (part "R-EU_R0805"))
    )
    (comp (ref "R20")
      (value "1K8")
      (footprint "eagle-import:R0805")
      (libsource (lib "eagle-import") (part "R-EU_R0805"))
    )
    (comp (ref "R21")
      (value "12K")
      (footprint "eagle-import:R0805")
      (libsource (lib "eagle-import") (part "R-EU_R0805"))
    )
    (comp (ref "R22")
      (value "47K")
      (footprint "eagle-import:R0805")
      (libsource (lib "eagle-import") (part "R-EU_R0805"))
    )
    (comp (ref "R23")
      (value "1K")
      (footprint "eagle-import:R0805")
      (libsource (lib "eagle-import") (part "R-EU_R0805"))
    )
    (comp (ref "SAR1")
      (value "PCB 2.4mm")
      (footprint "eagle-import:PCB-SAR_2.4MM")
      (libsource (lib "eagle-import") (part "SARPCB-2.4MM"))
    )
    (comp (ref "SAR2")
      (value "PCB 2.4mm")
      (footprint "eagle-import:PCB-SAR_2.4MM")
      (libsource (lib "eagle-import") (part "SARPCB-2.4MM"))
    )
    (comp (ref "TP1")
      (value "PCB_TEST_TABSHIELD")
      (footprint "eagle-import:PCB_SHIELD_TAB")
      (libsource (lib "eagle-import") (part "PCB_TEST_TABSHIELD"))
    )
    (comp (ref "TR1")
      (value "Feryster 5572")
      (footprint "eagle-import:FERYSTER_5572")
      (libsource (lib "eagle-import") (part "FERYSTER_5572"))
    )
    (comp (ref "X1")
      (value "B2B-ZR")
      (footprint "eagle-import:B2B-ZR")
      (libsource (lib "eagle-import") (part "B2B-ZR"))
    )
    (comp (ref "X2")
      (value "39-30-1039")
      (footprint "eagle-import:MINIFIT_39301039_CRE")
      (libsource (lib "eagle-import") (part "MINIFIT_39301039-CREEPAGE"))
    )
    (comp (ref "ZD1")
      (value "BZX384-C13")
      (footprint "eagle-import:SOD323-W")
      (libsource (lib "eagle-import") (part "ZENER-DIODESOD323"))
    )
    (comp (ref "ZD2")
      (value "BZT52C20-DC")
      (footprint "eagle-import:SOD123")
      (libsource (lib "eagle-import") (part "ZENER-DIODESOD123"))
    )
    (comp (ref "ZD3")
      (value "MMSZ5230BT1G")
      (footprint "eagle-import:SOD323-W")
      (libsource (lib "eagle-import") (part "ZENER-DIODESOD323"))
    )
  )
  (nets
    (net (code "1") (name "+2.5VREF") (class "Default")
      (node (ref "C74") (pin "1") (pinfunction "1_1") (pintype "passive"))
      (node (ref "IC9") (pin "3") (pinfunction "+IN1_3") (pintype "input"))
      (node (ref "P1") (pin "E") (pinfunction "E_E") (pintype "passive"))
      (node (ref "R73") (pin "2") (pinfunction "2_2") (pintype "passive"))
      (node (ref "R79") (pin "1") (pinfunction "1_1") (pintype "passive"))
    )
    (net (code "2") (name "+5VREF") (class "Default")
      (node (ref "C48") (pin "2") (pinfunction "2_2") (pintype "passive"))
      (node (ref "C53") (pin "1") (pinfunction "1_1") (pintype "passive"))
      (node (ref "IC5") (pin "4") (pinfunction "REF_4") (pintype "output"))
      (node (ref "NTC1") (pin "1") (pinfunction "P$1_1") (pintype "bidirectional"))
      (node (ref "R37") (pin "1") (pinfunction "1_1") (pintype "passive"))
      (node (ref "R53") (pin "1") (pinfunction "1_1") (pintype "passive"))
      (node (ref "R57") (pin "2") (pinfunction "2_2") (pintype "passive"))
      (node (ref "X4") (pin "1") (pinfunction "1_1") (pintype "passive"))
    )
    (net (code "3") (name "+6V") (class "Default")
      (node (ref "C22") (pin "1") (pinfunction "1_1") (pintype "passive"))
      (node (ref "C25") (pin "1") (pinfunction "1_1") (pintype "passive"))
      (node (ref "D7") (pin "C") (pinfunction "C_C") (pintype "passive"))
      (node (ref "IC2") (pin "8") (pinfunction "IN_8") (pintype "power_in"))
      (node (ref "L4") (pin "2") (pinfunction "2_2") (pintype "passive"))
      (node (ref "LED1") (pin "A") (pinfunction "A_A") (pintype "passive"))
      (node (ref "R23") (pin "2") (pinfunction "2_2") (pintype "passive"))
      (node (ref "R66") (pin "1") (pinfunction "1_1") (pintype "passive"))
    )
    (net (code "4") (name "+12V") (class "Default")
      (node (ref "C29") (pin "2") (pinfunction "2_2") (pintype "passive"))
      (node (ref "C30") (pin "2") (pinfunction "2_2") (pintype "passive"))
      (node (ref "C52") (pin "1") (pinfunction "1_1") (pintype "passive"))
      (node (ref "C6") (pin "1") (pinfunction "1_1") (pintype "passive"))
      (node (ref "IC6") (pin "8") (pinfunction "V+_8") (pintype "power_in"))
      (node (ref "OK2") (pin "1") (pinfunction "A_1") (pintype "passive"))
      (node (ref "Q1") (pin "3") (pinfunction "E_3") (pintype "passive"))
      (node (ref "R27") (pin "2") (pinfunction "2_2") (pintype "passive"))
      (node (ref "R38") (pin "2") (pinfunction "2_2") (pintype "passive"))
      (node (ref "R45") (pin "2") (pinfunction "2_2") (pintype "passive"))
      (node (ref "X1") (pin "1") (pinfunction "1_1") (pintype "passive"))
    )
    (net (code "5") (name "+15V") (class "Default")
      (node (ref "D2") (pin "A") (pinfunction "A_A") (pintype "passive"))
      (node (ref "R5") (pin "1") (pinfunction "1_1") (pintype "passive"))
      (node (ref "TR1") (pin "15") (pinfunction "S3_DOT_15") (pintype "passive"))
    )
    (net (code "6") (name "-9V") (class "Default")
      (node (ref "C15") (pin "2") (pinfunction "2_2") (pintype "passive"))
      (node (ref "C16") (pin "2") (pinfunction "2_2") (pintype "passive"))
      (node (ref "D6") (pin "A") (pinfunction "A_A") (pintype "passive"))
      (node (ref "IC1") (pin "2") (pinfunction "IN_2") (pintype "input"))
      (node (ref "IC1") (pin "3") (pinfunction "IN_3") (pintype "input"))
      (node (ref "IC1") (pin "6") (pinfunction "IN_6") (pintype "input"))
      (node (ref "IC1") (pin "7") (pinfunction "IN_7") (pintype "input"))
      (node (ref "L3") (pin "2") (pinfunction "2_2") (pintype "passive"))
      (node (ref "X3") (pin "8") (pinfunction "S_8") (pintype "passive"))
    )
    (net (code "7") (name "-15V") (class "Default")
      (node (ref "C11") (pin "2") (pinfunction "-_2") (pintype "passive"))
      (node (ref "C12") (pin "2") (pinfunction "2_2") (pintype "passive"))
      (node (ref "JP1") (pin "COM") (pinfunction "COM_COM") (pintype "passive"))
      (node (ref "TR1") (pin "14") (pinfunction "S3_14") (pintype "passive"))
      (node (ref "X3") (pin "2") (pinfunction "S_2") (pintype "passive"))
    )
    (net (code "8") (name "0V") (class "Default")
      (node (ref "C13") (pin "-") (pinfunction "-_-") (pintype "passive"))
      (node (ref "C20") (pin "2") (pinfunction "2_2") (pintype "passive"))
      (node (ref "C27") (pin "2") (pinfunction "2_2") (pintype "passive"))
      (node (ref "C28") (pin "2") (pinfunction "2_2") (pintype "passive"))
      (node (ref "C29") (pin "1") (pinfunction "1_1") (pintype "passive"))
      (node (ref "C30") (pin "1") (pinfunction "1_1") (pintype "passive"))
      (node (ref "C31") (pin "-") (pinfunction "-_-") (pintype "passive"))
      (node (ref "C32") (pin "-") (pinfunction "-_-") (pintype "passive"))
      (node (ref "C36") (pin "1") (pinfunction "1_1") (pintype "passive"))
      (node (ref "C38") (pin "2") (pinfunction "2_2") (pintype "passive"))
      (node (ref "C39") (pin "2") (pinfunction "2_2") (pintype "passive"))
      (node (ref "C40") (pin "2") (pinfunction "2_2") (pintype "passive"))
      (node (ref "C43") (pin "2") (pinfunction "2_2") (pintype "passive"))
      (node (ref "C44") (pin "2") (pinfunction "2_2") (pintype "passive"))
      (node (ref "C46") (pin "1") (pinfunction "1_1") (pintype "passive"))
      (node (ref "C47") (pin "1") (pinfunction "1_1") (pintype "passive"))
      (node (ref "C6") (pin "2") (pinfunction "2_2") (pintype "passive"))
      (node (ref "C7") (pin "2") (pinfunction "-_2") (pintype "passive"))
      (node (ref "C8") (pin "2") (pinfunction "2_2") (pintype "passive"))
      (node (ref "D11") (pin "A") (pinfunction "A_A") (pintype "passive"))
      (node (ref "D15") (pin "2") (pinfunction "A_2") (pintype "passive"))
      (node (ref "IC3") (pin "1") (pinfunction "GND_1") (pintype "passive"))
      (node (ref "IC3") (pin "2") (pinfunction "GND_2") (pintype "passive"))
      (node (ref "IC3") (pin "3") (pinfunction "GND_3") (pintype "passive"))
      (node (ref "IC3") (pin "4") (pinfunction "GND_4") (pintype "passive"))
      (node (ref "IC4") (pin "9") (pinfunction "GNDB_9") (pintype "power_in"))
      (node (ref "JP2") (pin "NO") (pinfunction "NO_NO") (pintype "passive"))
      (node (ref "JP3") (pin "1") (pinfunction "1_1") (pintype "passive"))
      (node (ref "OK1") (pin "3") (pinfunction "EMIT_3") (pintype "passive"))
      (node (ref "Q3") (pin "S") (pinfunction "S_S") (pintype "passive"))
      (node (ref "Q4") (pin "S") (pinfunction "S_S") (pintype "passive"))
      (node (ref "Q6") (pin "S") (pinfunction "S_S") (pintype "passive"))
      (node (ref "R20") (pin "2") (pinfunction "2_2") (pintype "passive"))
      (node (ref "R21") (pin "1") (pinfunction "1_1") (pintype "passive"))
      (node (ref "R22") (pin "2") (pinfunction "2_2") (pintype "passive"))
      (node (ref "R39") (pin "2") (pinfunction "2_2") (pintype "passive"))
      (node (ref "R41") (pin "1") (pinfunction "1_1") (pintype "passive"))
      (node (ref "R41") (pin "2") (pinfunction "2_2") (pintype "passive"))
      (node (ref "SH1") (pin "P$2") (pinfunction "GND_B_P$2") (pintype "bidirectional"))
      (node (ref "TP3") (pin "1") (pinfunction "P$1_1") (pintype "bidirectional"))
      (node (ref "TR1") (pin "6") (pinfunction "S_BIAS_6") (pintype "passive"))
      (node (ref "X1") (pin "2") (pinfunction "1_2") (pintype "passive"))
      (node (ref "ZD1") (pin "A") (pinfunction "A_A") (pintype "passive"))
      (node (ref "ZD2") (pin "A") (pinfunction "A_A") (pintype "passive"))
    )
    (net (code "9") (name "6VAC") (class "Default")
      (node (ref "D8") (pin "A") (pinfunction "A_A") (pintype "passive"))
      (node (ref "R13") (pin "1") (pinfunction "1_1") (pintype "passive"))
      (node (ref "TR1") (pin "12") (pinfunction "S1_DOT_12") (pintype "passive"))
      (node (ref "TR1") (pin "13") (pinfunction "S1_DOT_13") (pintype "passive"))
    )
    (net (code "10") (name "7VAC") (class "Default")
      (node (ref "D5") (pin "C") (pinfunction "C_C") (pintype "passive"))
      (node (ref "R10") (pin "1") (pinfunction "1_1") (pintype "passive"))
      (node (ref "TR1") (pin "8") (pinfunction "S2_8") (pintype "passive"))
    )
    (net (code "11") (name "AGND") (class "Default")
      (node (ref "C37") (pin "1") (pinfunction "1_1") (pintype "passive"))
      (node (ref "C42") (pin "2") (pinfunction "2_2") (pintype "passive"))
      (node (ref "C45") (pin "1") (pinfunction "1_1") (pintype "passive"))
      (node (ref "C48") (pin "1") (pinfunction "1_1") (pintype "passive"))
      (node (ref "C49") (pin "1") (pinfunction "1_1") (pintype "passive"))
      (node (ref "C50") (pin "1") (pinfunction "1_1") (pintype "passive"))
      (node (ref "C51") (pin "1") (pinfunction "1_1") (pintype "passive"))
      (node (ref "C52") (pin "2") (pinfunction "2_2") (pintype "passive"))
      (node (ref "C53") (pin "2") (pinfunction "2_2") (pintype "passive"))
      (node (ref "IC4") (pin "4") (pinfunction "GNDI_4") (pintype "power_in"))
      (node (ref "IC4") (pin "5") (pinfunction "DISABLE_5") (pintype "input"))
      (node (ref "IC5") (pin "10") (pinfunction "PGND_10") (pintype "power_in"))
      (node (ref "IC5") (pin "11") (pinfunction "AGND_11") (pintype "power_in"))
      (node (ref "IC5") (pin "2") (pinfunction "FB_2") (pintype "input"))
      (node (ref "IC6") (pin "4") (pinfunction "V-_4") (pintype "power_in"))
      (node (ref "JP3") (pin "2") (pinfunction "2_2") (pintype "passive"))
      (node (ref "OK3") (pin "3") (pinfunction "EMIT_3") (pintype "passive"))
      (node (ref "Q5") (pin "1") (pinfunction "C_1") (pintype "passive"))
      (node (ref "Q7") (pin "C") (pinfunction "C_C") (pintype "passive"))
      (node (ref "R24") (pin "2") (pinfunction "2_2") (pintype "passive"))
      (node (ref "R25") (pin "2") (pinfunction "2_2") (pintype "passive"))
      (node (ref "R26") (pin "2") (pinfunction "2_2") (pintype "passive"))
      (node (ref "R33") (pin "1") (pinfunction "1_1") (pintype "passive"))
      (node (ref "R33") (pin "2") (pinfunction "2_2") (pintype "passive"))
      (node (ref "R34") (pin "1") (pinfunction "1_1") (pintype "passive"))
      (node (ref "R47") (pin "2") (pinfunction "2_2") (pintype "passive"))
      (node (ref "R51") (pin "2") (pinfunction "2_2") (pintype "passive"))
      (node (ref "R52") (pin "2") (pinfunction "2_2") (pintype "passive"))
      (node (ref "R55") (pin "2") (pinfunction "2_2") (pintype "passive"))
      (node (ref "R58") (pin "2") (pinfunction "2_2") (pintype "passive"))
      (node (ref "R59") (pin "2") (pinfunction "2_2") (pintype "passive"))
      (node (ref "R60") (pin "2") (pinfunction "2_2") (pintype "passive"))
      (node (ref "TR2") (pin "1") (pinfunction "S_DOT_1") (pintype "passive"))
      (node (ref "ZD4") (pin "A") (pinfunction "A_A") (pintype "passive"))
      (node (ref "ZD5") (pin "A") (pinfunction "A_A") (pintype "passive"))
    )
    (net (code "12") (name "AUX_AC") (class "Default")
      (node (ref "D1") (pin "A") (pinfunction "A_A") (pintype "passive"))
      (node (ref "D10") (pin "A") (pinfunction "A_A") (pintype "passive"))
      (node (ref "R12") (pin "2") (pinfunction "2_2") (pintype "passive"))
      (node (ref "R3") (pin "1") (pinfunction "1_1") (pintype "passive"))
      (node (ref "TR1") (pin "7") (pinfunction "S_BIAS_DOT_7") (pintype "passive"))
    )
    (net (code "13") (name "AUX_DC") (class "Default")
      (node (ref "C3") (pin "2") (pinfunction "2_2") (pintype "passive"))
      (node (ref "C7") (pin "1") (pinfunction "+_1") (pintype "passive"))
      (node (ref "D1") (pin "C") (pinfunction "C_C") (pintype "passive"))
      (node (ref "Q1") (pin "2") (pinfunction "C_2") (pintype "passive"))
      (node (ref "Q1") (pin "4") (pinfunction "C_4") (pintype "passive"))
      (node (ref "R11") (pin "1") (pinfunction "1_1") (pintype "passive"))
      (node (ref "R4") (pin "1") (pinfunction "1_1") (pintype "passive"))
    )
    (net (code "14") (name "BUCK_OUT") (class "Default")
      (node (ref "C33") (pin "2") (pinfunction "2_2") (pintype "passive"))
      (node (ref "C34") (pin "2") (pinfunction "2_2") (pintype "passive"))
      (node (ref "C35") (pin "2") (pinfunction "2_2") (pintype "passive"))
      (node (ref "D15") (pin "1") (pinfunction "C_1") (pintype "passive"))
      (node (ref "IC4") (pin "14") (pinfunction "GNDA_14") (pintype "power_in"))
      (node (ref "L5") (pin "2") (pinfunction "P$2_2") (pintype "bidirectional"))
      (node (ref "L6") (pin "2") (pinfunction "P$2_2") (pintype "bidirectional"))
      (node (ref "Q2") (pin "S") (pinfunction "S_S") (pintype "passive"))
      (node (ref "Q3") (pin "D") (pinfunction "D_D") (pintype "passive"))
      (node (ref "TP2") (pin "1") (pinfunction "P$1_1") (pintype "bidirectional"))
    )
    (net (code "15") (name "CT_OUT") (class "Default")
      (node (ref "D12") (pin "C") (pinfunction "C_C") (pintype "passive"))
      (node (ref "R25") (pin "1") (pinfunction "1_1") (pintype "passive"))
      (node (ref "R26") (pin "1") (pinfunction "1_1") (pintype "passive"))
      (node (ref "R54") (pin "1") (pinfunction "1_1") (pintype "passive"))
    )
    (net (code "16") (name "DC_BUS") (class "Default")
      (node (ref "B1") (pin "+") (pinfunction "+_+") (pintype "passive"))
      (node (ref "C10") (pin "1") (pinfunction "1_1") (pintype "passive"))
      (node (ref "C13") (pin "+") (pinfunction "+_+") (pintype "passive"))
      (node (ref "C31") (pin "+") (pinfunction "+_+") (pintype "passive"))
      (node (ref "C32") (pin "+") (pinfunction "+_+") (pintype "passive"))
      (node (ref "C36") (pin "2") (pinfunction "2_2") (pintype "passive"))
      (node (ref "R36") (pin "1") (pinfunction "1_1") (pintype "passive"))
      (node (ref "R42") (pin "2") (pinfunction "2_2") (pintype "passive"))
      (node (ref "R43") (pin "2") (pinfunction "2_2") (pintype "passive"))
      (node (ref "R6") (pin "1") (pinfunction "1_1") (pintype "passive"))
      (node (ref "R7") (pin "1") (pinfunction "1_1") (pintype "passive"))
      (node (ref "TR1") (pin "1") (pinfunction "SHIELD_1") (pintype "passive"))
      (node (ref "TR1") (pin "2") (pinfunction "P_2") (pintype "passive"))
      (node (ref "TR2") (pin "7") (pinfunction "P_7") (pintype "passive"))
    )
    (net (code "17") (name "DC_OUT") (class "Default")
      (node (ref "C12") (pin "1") (pinfunction "1_1") (pintype "passive"))
      (node (ref "L2") (pin "2") (pinfunction "2_2") (pintype "passive"))
      (node (ref "X3") (pin "3") (pinfunction "S_3") (pintype "passive"))
    )
    (net (code "18") (name "GND") (class "Default")
      (node (ref "C14") (pin "1") (pinfunction "+_1") (pintype "passive"))
      (node (ref "C15") (pin "1") (pinfunction "1_1") (pintype "passive"))
      (node (ref "C16") (pin "1") (pinfunction "1_1") (pintype "passive"))
      (node (ref "C17") (pin "1") (pinfunction "1_1") (pintype "passive"))
      (node (ref "C18") (pin "2") (pinfunction "2_2") (pintype "passive"))
      (node (ref "C22") (pin "2") (pinfunction "2_2") (pintype "passive"))
      (node (ref "C23") (pin "-") (pinfunction "-_-") (pintype "passive"))
      (node (ref "C24") (pin "-") (pinfunction "-_-") (pintype "passive"))
      (node (ref "C25") (pin "2") (pinfunction "2_2") (pintype "passive"))
      (node (ref "C54") (pin "-") (pinfunction "-_-") (pintype "passive"))
      (node (ref "C55") (pin "-") (pinfunction "-_-") (pintype "passive"))
      (node (ref "C56") (pin "-") (pinfunction "-_-") (pintype "passive"))
      (node (ref "C57") (pin "2") (pinfunction "2_2") (pintype "passive"))
      (node (ref "C58") (pin "2") (pinfunction "2_2") (pintype "passive"))
      (node (ref "C59") (pin "2") (pinfunction "2_2") (pintype "passive"))
      (node (ref "C60") (pin "2") (pinfunction "2_2") (pintype "passive"))
      (node (ref "C61") (pin "2") (pinfunction "2_2") (pintype "passive"))
      (node (ref "C62") (pin "1") (pinfunction "1_1") (pintype "passive"))
      (node (ref "C63") (pin "2") (pinfunction "2_2") (pintype "passive"))
      (node (ref "C64") (pin "2") (pinfunction "2_2") (pintype "passive"))
      (node (ref "C65") (pin "2") (pinfunction "2_2") (pintype "passive"))
      (node (ref "C66") (pin "2") (pinfunction "2_2") (pintype "passive"))
      (node (ref "C67") (pin "2") (pinfunction "2_2") (pintype "passive"))
      (node (ref "C68") (pin "2") (pinfunction "2_2") (pintype "passive"))
      (node (ref "C69") (pin "2") (pinfunction "2_2") (pintype "passive"))
      (node (ref "C73") (pin "-") (pinfunction "-_-") (pintype "passive"))
      (node (ref "C74") (pin "2") (pinfunction "2_2") (pintype "passive"))
      (node (ref "D4") (pin "C") (pinfunction "C_C") (pintype "passive"))
      (node (ref "D9") (pin "A") (pinfunction "A_A") (pintype "passive"))
      (node (ref "IC1") (pin "5") (pinfunction "GND_5") (pintype "passive"))
      (node (ref "IC10") (pin "3") (pinfunction "A_3") (pintype "passive"))
      (node (ref "IC2") (pin "4") (pinfunction "GND_4") (pintype "passive"))
      (node (ref "IC7") (pin "6") (pinfunction "VS_6") (pintype "passive"))
      (node (ref "IC7") (pin "7") (pinfunction "GND_7") (pintype "power_in"))
      (node (ref "IC8") (pin "3") (pinfunction "+IN_3") (pintype "input"))
      (node (ref "IC8") (pin "5") (pinfunction "+IN_5") (pintype "input"))
      (node (ref "IC9") (pin "4") (pinfunction "VCC-_4") (pintype "power_in"))
      (node (ref "JP1") (pin "NO") (pinfunction "NO_NO") (pintype "passive"))
      (node (ref "OK2") (pin "3") (pinfunction "EMIT_3") (pintype "passive"))
      (node (ref "P1") (pin "A") (pinfunction "A_A") (pintype "passive"))
      (node (ref "Q8") (pin "2") (pinfunction "S_2") (pintype "passive"))
      (node (ref "Q9") (pin "2") (pinfunction "S_2") (pintype "passive"))
      (node (ref "R17") (pin "2") (pinfunction "2_2") (pintype "passive"))
      (node (ref "R18") (pin "2") (pinfunction "2_2") (pintype "passive"))
      (node (ref "R67") (pin "2") (pinfunction "2_2") (pintype "passive"))
      (node (ref "R87") (pin "1") (pinfunction "1_1") (pintype "passive"))
      (node (ref "TP1") (pin "1") (pinfunction "P$1_1") (pintype "bidirectional"))
      (node (ref "TP6") (pin "GND") (pinfunction "GND_GND") (pintype "bidirectional"))
      (node (ref "TR1") (pin "10") (pinfunction "S1_10") (pintype "passive"))
      (node (ref "TR1") (pin "11") (pinfunction "S1_11") (pintype "passive"))
      (node (ref "TR1") (pin "9") (pinfunction "S2_DOT_9") (pintype "passive"))
      (node (ref "X3") (pin "6") (pinfunction "S_6") (pintype "passive"))
      (node (ref "X5") (pin "2") (pinfunction "1_2") (pintype "passive"))
      (node (ref "ZD3") (pin "A") (pinfunction "A_A") (pintype "passive"))
      (node (ref "ZD6") (pin "A") (pinfunction "A_A") (pintype "passive"))
    )
    (net (code "19") (name "GNDA") (class "Default")
      (node (ref "B1") (pin "-") (pinfunction "-_-") (pintype "passive"))
      (node (ref "SH1") (pin "P$1") (pinfunction "GND_A_P$1") (pintype "bidirectional"))
    )
    (net (code "20") (name "HD") (class "Default")
      (node (ref "IC5") (pin "5") (pinfunction "HD_5") (pintype "output"))
      (node (ref "R29") (pin "2") (pinfunction "2_2") (pintype "passive"))
    )
    (net (code "21") (name "HI_OUT") (class "Default")
      (node (ref "D14") (pin "A") (pinfunction "A_A") (pintype "passive"))
      (node (ref "IC4") (pin "15") (pinfunction "VOA_15") (pintype "output"))
      (node (ref "R28") (pin "2") (pinfunction "2_2") (pintype "passive"))
    )
    (net (code "22") (name "ISO_FB") (class "Default")
      (node (ref "C50") (pin "2") (pinfunction "2_2") (pintype "passive"))
      (node (ref "IC5") (pin "3") (pinfunction "COMP_3") (pintype "passive"))
      (node (ref "OK3") (pin "4") (pinfunction "COL_4") (pintype "passive"))
      (node (ref "Q7") (pin "E") (pinfunction "E_E") (pintype "passive"))
      (node (ref "R56") (pin "1") (pinfunction "1_1") (pintype "passive"))
      (node (ref "TP5") (pin "1") (pinfunction "P$1_1") (pintype "bidirectional"))
    )
    (net (code "23") (name "LD") (class "Default")
      (node (ref "IC5") (pin "6") (pinfunction "LD_6") (pintype "output"))
      (node (ref "R31") (pin "2") (pinfunction "2_2") (pintype "passive"))
    )
    (net (code "24") (name "LO_OUT") (class "Default")
      (node (ref "D17") (pin "A") (pinfunction "A_A") (pintype "passive"))
      (node (ref "IC4") (pin "10") (pinfunction "VOB_10") (pintype "output"))
      (node (ref "R35") (pin "1") (pinfunction "1_1") (pintype "passive"))
    )
    (net (code "25") (name "Net-(C3-Pad1)") (class "Default")
      (node (ref "C3") (pin "1") (pinfunction "1_1") (pintype "passive"))
      (node (ref "R3") (pin "2") (pinfunction "2_2") (pintype "passive"))
    )
    (net (code "26") (name "Net-(C9-Pad1)") (class "Default")
      (node (ref "C9") (pin "1") (pinfunction "1_1") (pintype "passive"))
      (node (ref "R5") (pin "2") (pinfunction "2_2") (pintype "passive"))
    )
    (net (code "27") (name "Net-(C10-Pad2)") (class "Default")
      (node (ref "C10") (pin "2") (pinfunction "2_2") (pintype "passive"))
      (node (ref "D3") (pin "C") (pinfunction "C_C") (pintype "passive"))
      (node (ref "R8") (pin "2") (pinfunction "2_2") (pintype "passive"))
    )
    (net (code "28") (name "Net-(C11-+)") (class "Default")
      (node (ref "C11") (pin "1") (pinfunction "+_1") (pintype "passive"))
      (node (ref "C9") (pin "2") (pinfunction "2_2") (pintype "passive"))
      (node (ref "D2") (pin "C") (pinfunction "C_C") (pintype "passive"))
      (node (ref "L2") (pin "1") (pinfunction "1_1") (pintype "passive"))
    )
    (net (code "29") (name "Net-(C14--)") (class "Default")
      (node (ref "C14") (pin "2") (pinfunction "-_2") (pintype "passive"))
      (node (ref "C19") (pin "2") (pinfunction "2_2") (pintype "passive"))
      (node (ref "D5") (pin "A") (pinfunction "A_A") (pintype "passive"))
      (node (ref "L3") (pin "1") (pinfunction "1_1") (pintype "passive"))
    )
    (net (code "30") (name "Net-(C18-Pad1)") (class "Default")
      (node (ref "C18") (pin "1") (pinfunction "1_1") (pintype "passive"))
      (node (ref "JP2") (pin "COM") (pinfunction "COM_COM") (pintype "passive"))
    )
    (net (code "31") (name "Net-(C19-Pad1)") (class "Default")
      (node (ref "C19") (pin "1") (pinfunction "1_1") (pintype "passive"))
      (node (ref "R10") (pin "2") (pinfunction "2_2") (pintype "passive"))
    )
    (net (code "32") (name "Net-(C21-Pad1)") (class "Default")
      (node (ref "C21") (pin "1") (pinfunction "1_1") (pintype "passive"))
      (node (ref "R13") (pin "2") (pinfunction "2_2") (pintype "passive"))
    )
    (net (code "33") (name "Net-(C21-Pad2)") (class "Default")
      (node (ref "C21") (pin "2") (pinfunction "2_2") (pintype "passive"))
      (node (ref "C24") (pin "+") (pinfunction "+_+") (pintype "passive"))
      (node (ref "D8") (pin "C") (pinfunction "C_C") (pintype "passive"))
      (node (ref "L4") (pin "1") (pinfunction "1_1") (pintype "passive"))
      (node (ref "R16") (pin "1") (pinfunction "1_1") (pintype "passive"))
    )
    (net (code "34") (name "Net-(C26-Pad1)") (class "Default")
      (node (ref "C26") (pin "1") (pinfunction "1_1") (pintype "passive"))
      (node (ref "R22") (pin "1") (pinfunction "1_1") (pintype "passive"))
    )
    (net (code "35") (name "Net-(C41-Pad1)") (class "Default")
      (node (ref "C41") (pin "1") (pinfunction "1_1") (pintype "passive"))
      (node (ref "R32") (pin "1") (pinfunction "1_1") (pintype "passive"))
    )
    (net (code "36") (name "Net-(C46-Pad2)") (class "Default")
      (node (ref "C46") (pin "2") (pinfunction "2_2") (pintype "passive"))
      (node (ref "C47") (pin "2") (pinfunction "2_2") (pintype "passive"))
      (node (ref "D18") (pin "1") (pinfunction "C_1") (pintype "passive"))
      (node (ref "D18") (pin "3") (pinfunction "C_3") (pintype "passive"))
      (node (ref "D19") (pin "1") (pinfunction "C_1") (pintype "passive"))
      (node (ref "D19") (pin "3") (pinfunction "C_3") (pintype "passive"))
      (node (ref "R42") (pin "1") (pinfunction "1_1") (pintype "passive"))
      (node (ref "R43") (pin "1") (pinfunction "1_1") (pintype "passive"))
    )
    (net (code "37") (name "Net-(C51-Pad2)") (class "Default")
      (node (ref "C51") (pin "2") (pinfunction "2_2") (pintype "passive"))
      (node (ref "R56") (pin "2") (pinfunction "2_2") (pintype "passive"))
    )
    (net (code "38") (name "Net-(C62-Pad2)") (class "Default")
      (node (ref "C62") (pin "2") (pinfunction "2_2") (pintype "passive"))
      (node (ref "R62") (pin "1") (pinfunction "1_1") (pintype "passive"))
    )
    (net (code "39") (name "Net-(C63-Pad1)") (class "Default")
      (node (ref "C63") (pin "1") (pinfunction "1_1") (pintype "passive"))
      (node (ref "R63") (pin "2") (pinfunction "2_2") (pintype "passive"))
      (node (ref "R64") (pin "2") (pinfunction "2_2") (pintype "passive"))
    )
    (net (code "40") (name "Net-(C67-Pad1)") (class "Default")
      (node (ref "C67") (pin "1") (pinfunction "1_1") (pintype "passive"))
      (node (ref "R69") (pin "2") (pinfunction "2_2") (pintype "passive"))
      (node (ref "R70") (pin "2") (pinfunction "2_2") (pintype "passive"))
    )
    (net (code "41") (name "Net-(C72-Pad2)") (class "Default")
      (node (ref "C72") (pin "2") (pinfunction "2_2") (pintype "passive"))
      (node (ref "R81") (pin "2") (pinfunction "2_2") (pintype "passive"))
    )
    (net (code "42") (name "Net-(C73-Pad+)") (class "Default")
      (node (ref "C73") (pin "+") (pinfunction "+_+") (pintype "passive"))
      (node (ref "R74") (pin "1") (pinfunction "1_1") (pintype "passive"))
      (node (ref "R83") (pin "1") (pinfunction "1_1") (pintype "passive"))
      (node (ref "R84") (pin "1") (pinfunction "1_1") (pintype "passive"))
    )
    (net (code "43") (name "Net-(C76-Pad2)") (class "Default")
      (node (ref "C76") (pin "2") (pinfunction "2_2") (pintype "passive"))
      (node (ref "R86") (pin "1") (pinfunction "1_1") (pintype "passive"))
    )
    (net (code "44") (name "Net-(D10-PadC)") (class "Default")
      (node (ref "D10") (pin "C") (pinfunction "C_C") (pintype "passive"))
      (node (ref "D11") (pin "C") (pinfunction "C_C") (pintype "passive"))
      (node (ref "R15") (pin "2") (pinfunction "2_2") (pintype "passive"))
    )
    (net (code "45") (name "Net-(D13-A)") (class "Default")
      (node (ref "D13") (pin "2") (pinfunction "A_2") (pintype "passive"))
      (node (ref "R27") (pin "1") (pinfunction "1_1") (pintype "passive"))
    )
    (net (code "46") (name "Net-(D14-PadC)") (class "Default")
      (node (ref "D14") (pin "C") (pinfunction "C_C") (pintype "passive"))
      (node (ref "Q2") (pin "G") (pinfunction "G_G") (pintype "passive"))
      (node (ref "R28") (pin "1") (pinfunction "1_1") (pintype "passive"))
    )
    (net (code "47") (name "Net-(D16-PadA)") (class "Default")
      (node (ref "D16") (pin "A") (pinfunction "A_A") (pintype "passive"))
      (node (ref "R38") (pin "1") (pinfunction "1_1") (pintype "passive"))
    )
    (net (code "48") (name "Net-(D17-PadC)") (class "Default")
      (node (ref "D17") (pin "C") (pinfunction "C_C") (pintype "passive"))
      (node (ref "Q3") (pin "G") (pinfunction "G_G") (pintype "passive"))
      (node (ref "R35") (pin "2") (pinfunction "2_2") (pintype "passive"))
      (node (ref "R39") (pin "1") (pinfunction "1_1") (pintype "passive"))
    )
    (net (code "49") (name "Net-(D18-A)") (class "Default")
      (node (ref "C41") (pin "2") (pinfunction "2_2") (pintype "passive"))
      (node (ref "D18") (pin "2") (pinfunction "A_2") (pintype "passive"))
      (node (ref "L6") (pin "1") (pinfunction "P$1_1") (pintype "bidirectional"))
      (node (ref "Q6") (pin "D") (pinfunction "D_D") (pintype "passive"))
      (node (ref "TR3") (pin "P1_DOT") (pinfunction "P_DOT_P1_DOT") (pintype "passive"))
    )
    (net (code "50") (name "Net-(D19-A)") (class "Default")
      (node (ref "D19") (pin "2") (pinfunction "A_2") (pintype "passive"))
      (node (ref "L5") (pin "1") (pinfunction "P$1_1") (pintype "bidirectional"))
      (node (ref "Q4") (pin "D") (pinfunction "D_D") (pintype "passive"))
      (node (ref "R30") (pin "2") (pinfunction "2_2") (pintype "passive"))
      (node (ref "TR3") (pin "P1") (pinfunction "P_P1") (pintype "passive"))
    )
    (net (code "51") (name "Net-(D20-PadA)") (class "Default")
      (node (ref "D20") (pin "A") (pinfunction "A_A") (pintype "passive"))
      (node (ref "LED2") (pin "C") (pinfunction "C_C") (pintype "passive"))
    )
    (net (code "52") (name "Net-(D22-PadC)") (class "Default")
      (node (ref "D22") (pin "C") (pinfunction "C_C") (pintype "passive"))
      (node (ref "Q4") (pin "G") (pinfunction "G_G") (pintype "passive"))
      (node (ref "R48") (pin "1") (pinfunction "1_1") (pintype "passive"))
    )
    (net (code "53") (name "Net-(D23-PadC)") (class "Default")
      (node (ref "D23") (pin "C") (pinfunction "C_C") (pintype "passive"))
      (node (ref "Q6") (pin "G") (pinfunction "G_G") (pintype "passive"))
      (node (ref "R49") (pin "1") (pinfunction "1_1") (pintype "passive"))
    )
    (net (code "54") (name "Net-(IC2-FB)") (class "Default")
      (node (ref "IC2") (pin "7") (pinfunction "FB_7") (pintype "input"))
      (node (ref "R14") (pin "2") (pinfunction "2_2") (pintype "passive"))
      (node (ref "R17") (pin "1") (pinfunction "1_1") (pintype "passive"))
    )
    (net (code "55") (name "Net-(IC3-BR)") (class "Default")
      (node (ref "IC3") (pin "8") (pinfunction "BR_8") (pintype "input"))
      (node (ref "R20") (pin "1") (pinfunction "1_1") (pintype "passive"))
      (node (ref "R9") (pin "2") (pinfunction "2_2") (pintype "passive"))
    )
    (net (code "56") (name "Net-(IC3-FB)") (class "Default")
      (node (ref "C26") (pin "2") (pinfunction "2_2") (pintype "passive"))
      (node (ref "C27") (pin "1") (pinfunction "1_1") (pintype "passive"))
      (node (ref "IC3") (pin "7") (pinfunction "FB_7") (pintype "input"))
      (node (ref "OK1") (pin "4") (pinfunction "COL_4") (pintype "passive"))
    )
    (net (code "57") (name "Net-(IC3-VDD)") (class "Default")
      (node (ref "C20") (pin "1") (pinfunction "1_1") (pintype "passive"))
      (node (ref "IC3") (pin "5") (pinfunction "VDD_5") (pintype "power_in"))
      (node (ref "R11") (pin "2") (pinfunction "2_2") (pintype "passive"))
      (node (ref "ZD2") (pin "C") (pinfunction "C_C") (pintype "passive"))
    )
    (net (code "58") (name "Net-(IC3-ZCD)") (class "Default")
      (node (ref "C28") (pin "1") (pinfunction "1_1") (pintype "passive"))
      (node (ref "IC3") (pin "6") (pinfunction "ZCD_6") (pintype "input"))
      (node (ref "R12") (pin "1") (pinfunction "1_1") (pintype "passive"))
      (node (ref "R15") (pin "1") (pinfunction "1_1") (pintype "passive"))
      (node (ref "R21") (pin "2") (pinfunction "2_2") (pintype "passive"))
    )
    (net (code "59") (name "Net-(IC4-DT)") (class "Default")
      (node (ref "IC4") (pin "6") (pinfunction "DT_6") (pintype "input"))
      (node (ref "R34") (pin "2") (pinfunction "2_2") (pintype "passive"))
    )
    (net (code "60") (name "Net-(IC4-VDDA)") (class "Default")
      (node (ref "C33") (pin "1") (pinfunction "1_1") (pintype "passive"))
      (node (ref "C34") (pin "1") (pinfunction "1_1") (pintype "passive"))
      (node (ref "C35") (pin "1") (pinfunction "1_1") (pintype "passive"))
      (node (ref "D13") (pin "1") (pinfunction "C_1") (pintype "passive"))
      (node (ref "D13") (pin "3") (pinfunction "C_3") (pintype "passive"))
      (node (ref "IC4") (pin "16") (pinfunction "VDDA_16") (pintype "power_in"))
    )
    (net (code "61") (name "Net-(IC4-VDDB)") (class "Default")
      (node (ref "C38") (pin "1") (pinfunction "1_1") (pintype "passive"))
      (node (ref "C39") (pin "1") (pinfunction "1_1") (pintype "passive"))
      (node (ref "C40") (pin "1") (pinfunction "1_1") (pintype "passive"))
      (node (ref "D16") (pin "C") (pinfunction "C_C") (pintype "passive"))
      (node (ref "IC4") (pin "11") (pinfunction "VDDB_11") (pintype "power_in"))
    )
    (net (code "62") (name "Net-(IC4-VIA)") (class "Default")
      (node (ref "IC4") (pin "1") (pinfunction "VIA_1") (pintype "input"))
      (node (ref "R29") (pin "1") (pinfunction "1_1") (pintype "passive"))
    )
    (net (code "63") (name "Net-(IC4-VIB)") (class "Default")
      (node (ref "IC4") (pin "2") (pinfunction "VIB_2") (pintype "input"))
      (node (ref "R31") (pin "1") (pinfunction "1_1") (pintype "passive"))
    )
    (net (code "64") (name "Net-(IC5-CS)") (class "Default")
      (node (ref "C49") (pin "2") (pinfunction "2_2") (pintype "passive"))
      (node (ref "IC5") (pin "12") (pinfunction "CS_12") (pintype "input"))
      (node (ref "R54") (pin "2") (pinfunction "2_2") (pintype "passive"))
    )
    (net (code "65") (name "Net-(IC5-RT{slash}SYNC)") (class "Default")
      (node (ref "IC5") (pin "15") (pinfunction "RT/SYNC_15") (pintype "input"))
      (node (ref "R52") (pin "1") (pinfunction "1_1") (pintype "passive"))
    )
    (net (code "66") (name "Net-(IC5-SS)") (class "Default")
      (node (ref "C45") (pin "2") (pinfunction "2_2") (pintype "passive"))
      (node (ref "IC5") (pin "13") (pinfunction "SS_13") (pintype "passive"))
    )
    (net (code "67") (name "Net-(IC5-TIME)") (class "Default")
      (node (ref "IC5") (pin "14") (pinfunction "TIME_14") (pintype "input"))
      (node (ref "R51") (pin "1") (pinfunction "1_1") (pintype "passive"))
    )
    (net (code "68") (name "Net-(IC5-UVLO)") (class "Default")
      (node (ref "IC5") (pin "16") (pinfunction "UVLO_16") (pintype "input"))
      (node (ref "R46") (pin "1") (pinfunction "1_1") (pintype "passive"))
      (node (ref "ZD5") (pin "C") (pinfunction "C_C") (pintype "passive"))
    )
    (net (code "69") (name "Net-(IC5-VCC)") (class "Default")
      (node (ref "C43") (pin "1") (pinfunction "1_1") (pintype "passive"))
      (node (ref "C44") (pin "1") (pinfunction "1_1") (pintype "passive"))
      (node (ref "IC5") (pin "1") (pinfunction "VIN_1") (pintype "input"))
      (node (ref "IC5") (pin "7") (pinfunction "VCC_7") (pintype "power_in"))
      (node (ref "R45") (pin "1") (pinfunction "1_1") (pintype "passive"))
    )
    (net (code "70") (name "Net-(IC6A-+IN)") (class "Default")
      (node (ref "IC6") (pin "3") (pinfunction "+IN_3") (pintype "input"))
      (node (ref "NTC1") (pin "2") (pinfunction "P$2_2") (pintype "bidirectional"))
      (node (ref "R60") (pin "1") (pinfunction "1_1") (pintype "passive"))
      (node (ref "X4") (pin "2") (pinfunction "1_2") (pintype "passive"))
    )
    (net (code "71") (name "Net-(IC6A--IN)") (class "Default")
      (node (ref "IC6") (pin "1") (pinfunction "OUT_1") (pintype "output"))
      (node (ref "IC6") (pin "2") (pinfunction "-IN_2") (pintype "input"))
      (node (ref "IC6") (pin "5") (pinfunction "+IN_5") (pintype "input"))
    )
    (net (code "72") (name "Net-(IC6B--IN)") (class "Default")
      (node (ref "IC6") (pin "6") (pinfunction "-IN_6") (pintype "input"))
      (node (ref "R57") (pin "1") (pinfunction "1_1") (pintype "passive"))
      (node (ref "R59") (pin "1") (pinfunction "1_1") (pintype "passive"))
    )
    (net (code "73") (name "Net-(IC6B-OUT)") (class "Default")
      (node (ref "IC6") (pin "7") (pinfunction "OUT_7") (pintype "output"))
      (node (ref "R50") (pin "2") (pinfunction "2_2") (pintype "passive"))
      (node (ref "R58") (pin "1") (pinfunction "1_1") (pintype "passive"))
    )
    (net (code "74") (name "Net-(IC7-GATE1)") (class "Default")
      (node (ref "D24") (pin "C") (pinfunction "C_C") (pintype "passive"))
      (node (ref "IC7") (pin "1") (pinfunction "GATE1_1") (pintype "output"))
      (node (ref "R65") (pin "2") (pinfunction "2_2") (pintype "passive"))
    )
    (net (code "75") (name "Net-(IC7-GATE2)") (class "Default")
      (node (ref "D25") (pin "C") (pinfunction "C_C") (pintype "passive"))
      (node (ref "IC7") (pin "8") (pinfunction "GATE2_8") (pintype "output"))
      (node (ref "R68") (pin "2") (pinfunction "2_2") (pintype "passive"))
    )
    (net (code "76") (name "Net-(IC7-MOT)") (class "Default")
      (node (ref "IC7") (pin "3") (pinfunction "MOT_3") (pintype "passive"))
      (node (ref "R67") (pin "1") (pinfunction "1_1") (pintype "passive"))
    )
    (net (code "77") (name "Net-(IC7-VCC)") (class "Default")
      (node (ref "C64") (pin "1") (pinfunction "1_1") (pintype "passive"))
      (node (ref "C65") (pin "1") (pinfunction "1_1") (pintype "passive"))
      (node (ref "IC7") (pin "2") (pinfunction "VCC_2") (pintype "power_in"))
      (node (ref "R66") (pin "2") (pinfunction "2_2") (pintype "passive"))
    )
    (net (code "78") (name "Net-(IC8A--IN)") (class "Default")
      (node (ref "C70") (pin "2") (pinfunction "2_2") (pintype "passive"))
      (node (ref "IC8") (pin "2") (pinfunction "-IN_2") (pintype "input"))
      (node (ref "R75") (pin "2") (pinfunction "2_2") (pintype "passive"))
      (node (ref "R76") (pin "1") (pinfunction "1_1") (pintype "passive"))
      (node (ref "R80") (pin "1") (pinfunction "1_1") (pintype "passive"))
    )
    (net (code "79") (name "Net-(IC8A-OUT)") (class "Default")
      (node (ref "C70") (pin "1") (pinfunction "1_1") (pintype "passive"))
      (node (ref "IC8") (pin "1") (pinfunction "OUT_1") (pintype "output"))
      (node (ref "R84") (pin "2") (pinfunction "2_2") (pintype "passive"))
    )
    (net (code "80") (name "Net-(IC8B--IN)") (class "Default")
      (node (ref "IC8") (pin "6") (pinfunction "-IN_6") (pintype "input"))
      (node (ref "R71") (pin "2") (pinfunction "2_2") (pintype "passive"))
      (node (ref "R73") (pin "1") (pinfunction "1_1") (pintype "passive"))
    )
    (net (code "81") (name "Net-(IC8B-OUT)") (class "Default")
      (node (ref "IC8") (pin "7") (pinfunction "OUT_7") (pintype "output"))
      (node (ref "R71") (pin "1") (pinfunction "1_1") (pintype "passive"))
      (node (ref "R76") (pin "2") (pinfunction "2_2") (pintype "passive"))
    )
    (net (code "82") (name "Net-(IC9A--IN1)") (class "Default")
      (node (ref "C71") (pin "2") (pinfunction "2_2") (pintype "passive"))
      (node (ref "IC9") (pin "2") (pinfunction "-IN1_2") (pintype "input"))
      (node (ref "R81") (pin "1") (pinfunction "1_1") (pintype "passive"))
      (node (ref "R82") (pin "1") (pinfunction "1_1") (pintype "passive"))
    )
    (net (code "83") (name "Net-(IC9B-+IN)") (class "Default")
      (node (ref "IC9") (pin "5") (pinfunction "+IN_5") (pintype "input"))
      (node (ref "JP4") (pin "COM") (pinfunction "COM_COM") (pintype "passive"))
    )
    (net (code "84") (name "Net-(IC9B--IN)") (class "Default")
      (node (ref "IC9") (pin "6") (pinfunction "-IN_6") (pintype "input"))
      (node (ref "IC9") (pin "7") (pinfunction "OUT_7") (pintype "output"))
      (node (ref "R80") (pin "2") (pinfunction "2_2") (pintype "passive"))
    )
    (net (code "85") (name "Net-(IC10-C)") (class "Default")
      (node (ref "C71") (pin "1") (pinfunction "1_1") (pintype "passive"))
      (node (ref "C72") (pin "1") (pinfunction "1_1") (pintype "passive"))
      (node (ref "C75") (pin "1") (pinfunction "1_1") (pintype "passive"))
      (node (ref "C76") (pin "1") (pinfunction "1_1") (pintype "passive"))
      (node (ref "IC10") (pin "1") (pinfunction "C_1") (pintype "passive"))
      (node (ref "IC9") (pin "1") (pinfunction "OUT1_1") (pintype "output"))
      (node (ref "OK3") (pin "2") (pinfunction "C_2") (pintype "passive"))
      (node (ref "R85") (pin "2") (pinfunction "2_2") (pintype "passive"))
    )
    (net (code "86") (name "Net-(IC10-REF)") (class "Default")
      (node (ref "C75") (pin "2") (pinfunction "2_2") (pintype "passive"))
      (node (ref "IC10") (pin "2") (pinfunction "REF_2") (pintype "passive"))
      (node (ref "R78") (pin "1") (pinfunction "1_1") (pintype "passive"))
      (node (ref "R82") (pin "2") (pinfunction "2_2") (pintype "passive"))
      (node (ref "R83") (pin "2") (pinfunction "2_2") (pintype "passive"))
      (node (ref "R86") (pin "2") (pinfunction "2_2") (pintype "passive"))
      (node (ref "R87") (pin "2") (pinfunction "2_2") (pintype "passive"))
      (node (ref "TP7") (pin "1") (pinfunction "P$1_1") (pintype "bidirectional"))
    )
    (net (code "87") (name "Net-(JP4-PadNO)") (class "Default")
      (node (ref "JP4") (pin "NO") (pinfunction "NO_NO") (pintype "passive"))
      (node (ref "P1") (pin "S") (pinfunction "S_S") (pintype "passive"))
    )
    (net (code "88") (name "Net-(L1B-1)") (class "Default")
      (node (ref "B1") (pin "AC2") (pinfunction "AC2_AC2") (pintype "passive"))
      (node (ref "C2") (pin "2") (pinfunction "2_2") (pintype "passive"))
      (node (ref "C4") (pin "2") (pinfunction "2_2") (pintype "passive"))
      (node (ref "L1") (pin "3") (pinfunction "1_3") (pintype "passive"))
      (node (ref "SAR2") (pin "2") (pinfunction "P$2_2") (pintype "bidirectional"))
    )
    (net (code "89") (name "Net-(L1B-2)") (class "Default")
      (node (ref "C1") (pin "2") (pinfunction "2_2") (pintype "passive"))
      (node (ref "C4A") (pin "2") (pinfunction "2_2") (pintype "passive"))
      (node (ref "L1") (pin "4") (pinfunction "2_4") (pintype "passive"))
      (node (ref "R2") (pin "2") (pinfunction "2_2") (pintype "passive"))
      (node (ref "SAR2") (pin "1") (pinfunction "P$1_1") (pintype "bidirectional"))
      (node (ref "X2") (pin "3") (pinfunction "1_3") (pintype "passive"))
    )
    (net (code "90") (name "Net-(LED1-PadC)") (class "Default")
      (node (ref "LED1") (pin "C") (pinfunction "C_C") (pintype "passive"))
      (node (ref "R18") (pin "1") (pinfunction "1_1") (pintype "passive"))
    )
    (net (code "91") (name "Net-(LED2-PadA)") (class "Default")
      (node (ref "LED2") (pin "A") (pinfunction "A_A") (pintype "passive"))
      (node (ref "R40") (pin "2") (pinfunction "2_2") (pintype "passive"))
    )
    (net (code "92") (name "Net-(OK1-A)") (class "Default")
      (node (ref "OK1") (pin "1") (pinfunction "A_1") (pintype "passive"))
      (node (ref "R16") (pin "2") (pinfunction "2_2") (pintype "passive"))
    )
    (net (code "93") (name "Net-(OK1-C)") (class "Default")
      (node (ref "OK1") (pin "2") (pinfunction "C_2") (pintype "passive"))
      (node (ref "R23") (pin "1") (pinfunction "1_1") (pintype "passive"))
      (node (ref "ZD3") (pin "C") (pinfunction "C_C") (pintype "passive"))
    )
    (net (code "94") (name "Net-(OK2-C)") (class "Default")
      (node (ref "OK2") (pin "2") (pinfunction "C_2") (pintype "passive"))
      (node (ref "R40") (pin "1") (pinfunction "1_1") (pintype "passive"))
    )
    (net (code "95") (name "Net-(OK3-A)") (class "Default")
      (node (ref "OK3") (pin "1") (pinfunction "A_1") (pintype "passive"))
      (node (ref "R77") (pin "1") (pinfunction "1_1") (pintype "passive"))
      (node (ref "R85") (pin "1") (pinfunction "1_1") (pintype "passive"))
    )
    (net (code "96") (name "Net-(Q1-B)") (class "Default")
      (node (ref "C8") (pin "1") (pinfunction "1_1") (pintype "passive"))
      (node (ref "Q1") (pin "1") (pinfunction "B_1") (pintype "passive"))
      (node (ref "R4") (pin "2") (pinfunction "2_2") (pintype "passive"))
      (node (ref "ZD1") (pin "C") (pinfunction "C_C") (pintype "passive"))
    )
    (net (code "97") (name "Net-(Q5-A)") (class "Default")
      (node (ref "D20") (pin "C") (pinfunction "C_C") (pintype "passive"))
      (node (ref "D21") (pin "C") (pinfunction "C_C") (pintype "passive"))
      (node (ref "Q5") (pin "3") (pinfunction "A_3") (pintype "passive"))
    )
    (net (code "98") (name "Net-(Q5-G)") (class "Default")
      (node (ref "Q5") (pin "2") (pinfunction "G_2") (pintype "passive"))
      (node (ref "R50") (pin "1") (pinfunction "1_1") (pintype "passive"))
    )
    (net (code "99") (name "Net-(Q7-PadB)") (class "Default")
      (node (ref "Q7") (pin "B") (pinfunction "B_B") (pintype "passive"))
      (node (ref "R53") (pin "2") (pinfunction "2_2") (pintype "passive"))
      (node (ref "R55") (pin "1") (pinfunction "1_1") (pintype "passive"))
    )
    (net (code "100") (name "Net-(R1-Pad2)") (class "Default")
      (node (ref "R1") (pin "2") (pinfunction "2_2") (pintype "passive"))
      (node (ref "R2") (pin "1") (pinfunction "1_1") (pintype "passive"))
    )
    (net (code "101") (name "Net-(R6-Pad2)") (class "Default")
      (node (ref "R6") (pin "2") (pinfunction "2_2") (pintype "passive"))
      (node (ref "R9") (pin "1") (pinfunction "1_1") (pintype "passive"))
    )
    (net (code "102") (name "Net-(R7-Pad2)") (class "Default")
      (node (ref "R7") (pin "2") (pinfunction "2_2") (pintype "passive"))
      (node (ref "R8") (pin "1") (pinfunction "1_1") (pintype "passive"))
    )
    (net (code "103") (name "Net-(R30-Pad1)") (class "Default")
      (node (ref "R30") (pin "1") (pinfunction "1_1") (pintype "passive"))
      (node (ref "R32") (pin "2") (pinfunction "2_2") (pintype "passive"))
    )
    (net (code "104") (name "Net-(R36-Pad2)") (class "Default")
      (node (ref "R36") (pin "2") (pinfunction "2_2") (pintype "passive"))
      (node (ref "R44") (pin "1") (pinfunction "1_1") (pintype "passive"))
    )
    (net (code "105") (name "Net-(R72-Pad1)") (class "Default")
      (node (ref "R72") (pin "1") (pinfunction "1_1") (pintype "passive"))
      (node (ref "R78") (pin "2") (pinfunction "2_2") (pintype "passive"))
    )
    (net (code "106") (name "Net-(R74-Pad2)") (class "Default")
      (node (ref "R74") (pin "2") (pinfunction "2_2") (pintype "passive"))
      (node (ref "R75") (pin "1") (pinfunction "1_1") (pintype "passive"))
    )
    (net (code "107") (name "Net-(SAR1-P$1)") (class "Default")
      (node (ref "C1") (pin "1") (pinfunction "1_1") (pintype "passive"))
      (node (ref "C2A") (pin "2") (pinfunction "2_2") (pintype "passive"))
      (node (ref "L1") (pin "2") (pinfunction "2_2") (pintype "passive"))
      (node (ref "R1") (pin "1") (pinfunction "1_1") (pintype "passive"))
      (node (ref "SAR1") (pin "1") (pinfunction "P$1_1") (pintype "bidirectional"))
      (node (ref "X2") (pin "2") (pinfunction "1_2") (pintype "passive"))
    )
    (net (code "108") (name "Net-(SAR1-P$2)") (class "Default")
      (node (ref "B1") (pin "AC1") (pinfunction "AC1_AC1") (pintype "passive"))
      (node (ref "C2") (pin "1") (pinfunction "1_1") (pintype "passive"))
      (node (ref "C5") (pin "2") (pinfunction "2_2") (pintype "passive"))
      (node (ref "L1") (pin "1") (pinfunction "1_1") (pintype "passive"))
      (node (ref "SAR1") (pin "2") (pinfunction "P$2_2") (pintype "bidirectional"))
    )
    (net (code "109") (name "Net-(TP4-P$1)") (class "Default")
      (node (ref "C42") (pin "1") (pinfunction "1_1") (pintype "passive"))
      (node (ref "D21") (pin "A") (pinfunction "A_A") (pintype "passive"))
      (node (ref "R44") (pin "2") (pinfunction "2_2") (pintype "passive"))
      (node (ref "R46") (pin "2") (pinfunction "2_2") (pintype "passive"))
      (node (ref "R47") (pin "1") (pinfunction "1_1") (pintype "passive"))
      (node (ref "TP4") (pin "1") (pinfunction "P$1_1") (pintype "bidirectional"))
    )
    (net (code "110") (name "Net-(TR2-P_DOT)") (class "Default")
      (node (ref "Q2") (pin "D") (pinfunction "D_D") (pintype "passive"))
      (node (ref "TR2") (pin "8") (pinfunction "P_DOT_8") (pintype "passive"))
    )
    (net (code "111") (name "Net-(TR2-S)") (class "Default")
      (node (ref "D12") (pin "A") (pinfunction "A_A") (pintype "passive"))
      (node (ref "R24") (pin "1") (pinfunction "1_1") (pintype "passive"))
      (node (ref "TR2") (pin "3") (pinfunction "S_3") (pintype "passive"))
    )
    (net (code "112") (name "PE") (class "Default")
      (node (ref "C2A") (pin "1") (pinfunction "1_1") (pintype "passive"))
      (node (ref "C4") (pin "1") (pinfunction "1_1") (pintype "passive"))
      (node (ref "C4A") (pin "1") (pinfunction "1_1") (pintype "passive"))
      (node (ref "C5") (pin "1") (pinfunction "1_1") (pintype "passive"))
      (node (ref "JP2") (pin "NC") (pinfunction "NC_NC") (pintype "passive"))
      (node (ref "X2") (pin "1") (pinfunction "1_1") (pintype "passive"))
    )
    (net (code "113") (name "POUT+") (class "Default")
      (node (ref "C54") (pin "+") (pinfunction "+_+") (pintype "passive"))
      (node (ref "C55") (pin "+") (pinfunction "+_+") (pintype "passive"))
      (node (ref "C56") (pin "+") (pinfunction "+_+") (pintype "passive"))
      (node (ref "C57") (pin "1") (pinfunction "1_1") (pintype "passive"))
      (node (ref "L7") (pin "1") (pinfunction "1_1") (pintype "passive"))
      (node (ref "R61") (pin "1") (pinfunction "1_1") (pintype "passive"))
      (node (ref "R72") (pin "2") (pinfunction "2_2") (pintype "passive"))
      (node (ref "SH2") (pin "P$2") (pinfunction "GND_B_P$2") (pintype "bidirectional"))
      (node (ref "SH3") (pin "P$1") (pinfunction "GND_A_P$1") (pintype "bidirectional"))
    )
    (net (code "114") (name "PREG_OUT+") (class "Default")
      (node (ref "C58") (pin "1") (pinfunction "1_1") (pintype "passive"))
      (node (ref "C59") (pin "1") (pinfunction "1_1") (pintype "passive"))
      (node (ref "C60") (pin "1") (pinfunction "1_1") (pintype "passive"))
      (node (ref "C61") (pin "1") (pinfunction "1_1") (pintype "passive"))
      (node (ref "JP1") (pin "NC") (pinfunction "NC_NC") (pintype "passive"))
      (node (ref "L7") (pin "2") (pinfunction "2_2") (pintype "passive"))
      (node (ref "R61") (pin "2") (pinfunction "2_2") (pintype "passive"))
      (node (ref "R62") (pin "2") (pinfunction "2_2") (pintype "passive"))
      (node (ref "TP6") (pin "TIP") (pinfunction "TIP_TIP") (pintype "bidirectional"))
      (node (ref "X5") (pin "1") (pinfunction "1_1") (pintype "passive"))
      (node (ref "ZD6") (pin "C") (pinfunction "C_C") (pintype "passive"))
    )
    (net (code "115") (name "PULL") (class "Default")
      (node (ref "D23") (pin "A") (pinfunction "A_A") (pintype "passive"))
      (node (ref "IC5") (pin "9") (pinfunction "PULL_9") (pintype "output"))
      (node (ref "R49") (pin "2") (pinfunction "2_2") (pintype "passive"))
    )
    (net (code "116") (name "PUSH") (class "Default")
      (node (ref "D22") (pin "A") (pinfunction "A_A") (pintype "passive"))
      (node (ref "IC5") (pin "8") (pinfunction "PUSH_8") (pintype "output"))
      (node (ref "R48") (pin "2") (pinfunction "2_2") (pintype "passive"))
    )
    (net (code "117") (name "PWRGOOD") (class "Default")
      (node (ref "IC2") (pin "5") (pinfunction "~{ERROR}_5") (pintype "input"))
      (node (ref "OK2") (pin "4") (pinfunction "COL_4") (pintype "passive"))
      (node (ref "R19") (pin "2") (pinfunction "2_2") (pintype "passive"))
      (node (ref "X3") (pin "4") (pinfunction "S_4") (pintype "passive"))
    )
    (net (code "118") (name "REF") (class "Default")
      (node (ref "C37") (pin "2") (pinfunction "2_2") (pintype "passive"))
      (node (ref "IC4") (pin "3") (pinfunction "VDDI_3") (pintype "power_in"))
      (node (ref "IC4") (pin "8") (pinfunction "VDDI_8") (pintype "power_in"))
      (node (ref "R37") (pin "2") (pinfunction "2_2") (pintype "passive"))
      (node (ref "ZD4") (pin "C") (pinfunction "C_C") (pintype "passive"))
    )
    (net (code "119") (name "S1_DOT_OUT") (class "Default")
      (node (ref "IC7") (pin "4") (pinfunction "VD1_4") (pintype "passive"))
      (node (ref "Q8") (pin "3") (pinfunction "D_3") (pintype "passive"))
      (node (ref "R63") (pin "1") (pinfunction "1_1") (pintype "passive"))
      (node (ref "R64") (pin "1") (pinfunction "1_1") (pintype "passive"))
      (node (ref "TR3") (pin "S1_DOT") (pinfunction "S1_DOT_S1_DOT") (pintype "passive"))
    )
    (net (code "120") (name "S1_OUT") (class "Default")
      (node (ref "SH2") (pin "P$1") (pinfunction "GND_A_P$1") (pintype "bidirectional"))
      (node (ref "TR3") (pin "S1") (pinfunction "S1_S1") (pintype "passive"))
    )
    (net (code "121") (name "S2_DOT_OUT") (class "Default")
      (node (ref "SH3") (pin "P$2") (pinfunction "GND_B_P$2") (pintype "bidirectional"))
      (node (ref "TR3") (pin "S2_DOT") (pinfunction "S2_DOT_S2_DOT") (pintype "passive"))
    )
    (net (code "122") (name "S2_OUT") (class "Default")
      (node (ref "IC7") (pin "5") (pinfunction "VD2_5") (pintype "passive"))
      (node (ref "Q9") (pin "3") (pinfunction "D_3") (pintype "passive"))
      (node (ref "R69") (pin "1") (pinfunction "1_1") (pintype "passive"))
      (node (ref "R70") (pin "1") (pinfunction "1_1") (pintype "passive"))
      (node (ref "TR3") (pin "S2") (pinfunction "S2_S2") (pintype "passive"))
    )
    (net (code "123") (name "SR_OUT1") (class "Default")
      (node (ref "D24") (pin "A") (pinfunction "A_A") (pintype "passive"))
      (node (ref "Q8") (pin "1") (pinfunction "G_1") (pintype "passive"))
      (node (ref "R65") (pin "1") (pinfunction "1_1") (pintype "passive"))
    )
    (net (code "124") (name "SR_OUT2") (class "Default")
      (node (ref "D25") (pin "A") (pinfunction "A_A") (pintype "passive"))
      (node (ref "Q9") (pin "1") (pinfunction "G_1") (pintype "passive"))
      (node (ref "R68") (pin "1") (pinfunction "1_1") (pintype "passive"))
    )
    (net (code "125") (name "U_MON") (class "Default")
      (node (ref "JP4") (pin "NC") (pinfunction "NC_NC") (pintype "passive"))
      (node (ref "X3") (pin "1") (pinfunction "S_1") (pintype "passive"))
    )
    (net (code "126") (name "V+") (class "Default")
      (node (ref "C23") (pin "+") (pinfunction "+_+") (pintype "passive"))
      (node (ref "C66") (pin "1") (pinfunction "1_1") (pintype "passive"))
      (node (ref "C69") (pin "1") (pinfunction "1_1") (pintype "passive"))
      (node (ref "D7") (pin "A") (pinfunction "A_A") (pintype "passive"))
      (node (ref "D9") (pin "C") (pinfunction "C_C") (pintype "passive"))
      (node (ref "IC2") (pin "1") (pinfunction "OUT_1") (pintype "output"))
      (node (ref "IC8") (pin "8") (pinfunction "V+_8") (pintype "power_in"))
      (node (ref "IC9") (pin "8") (pinfunction "VCC+_8") (pintype "power_in"))
      (node (ref "R14") (pin "1") (pinfunction "1_1") (pintype "passive"))
      (node (ref "R19") (pin "1") (pinfunction "1_1") (pintype "passive"))
      (node (ref "R77") (pin "2") (pinfunction "2_2") (pintype "passive"))
      (node (ref "R79") (pin "2") (pinfunction "2_2") (pintype "passive"))
      (node (ref "X3") (pin "5") (pinfunction "S_5") (pintype "passive"))
    )
    (net (code "127") (name "V-") (class "Default")
      (node (ref "C17") (pin "2") (pinfunction "2_2") (pintype "passive"))
      (node (ref "C68") (pin "1") (pinfunction "1_1") (pintype "passive"))
      (node (ref "D4") (pin "A") (pinfunction "A_A") (pintype "passive"))
      (node (ref "D6") (pin "C") (pinfunction "C_C") (pintype "passive"))
      (node (ref "IC1") (pin "1") (pinfunction "OUT_1") (pintype "passive"))
      (node (ref "IC8") (pin "4") (pinfunction "V-_4") (pintype "power_in"))
      (node (ref "X3") (pin "7") (pinfunction "S_7") (pintype "passive"))
    )
    (net (code "128") (name "VIPER_D") (class "Default")
      (node (ref "D3") (pin "A") (pinfunction "A_A") (pintype "passive"))
      (node (ref "IC3") (pin "13") (pinfunction "DRAIN_13") (pintype "output"))
      (node (ref "IC3") (pin "14") (pinfunction "DRAIN_14") (pintype "output"))
      (node (ref "IC3") (pin "15") (pinfunction "DRAIN_15") (pintype "output"))
      (node (ref "IC3") (pin "16") (pinfunction "DRAIN_16") (pintype "output"))
      (node (ref "TR1") (pin "4") (pinfunction "P2_DOT_4") (pintype "passive"))
    )
    (net (code "129") (name "unconnected-(IC2-SD-Pad3)") (class "Default")
      (node (ref "IC2") (pin "3") (pinfunction "SD_3") (pintype "input"))
    )
    (net (code "130") (name "unconnected-(IC2-SENSE-Pad2)") (class "Default")
      (node (ref "IC2") (pin "2") (pinfunction "SENSE_2") (pintype "input"))
    )
    (net (code "131") (name "unconnected-(IC2-VTAP-Pad6)") (class "Default")
      (node (ref "IC2") (pin "6") (pinfunction "VTAP_6") (pintype "input"))
    )
  )
)
